# CX3_Camera_Layout.net
KiCad netlist of a schematic drawn in Altium Designer
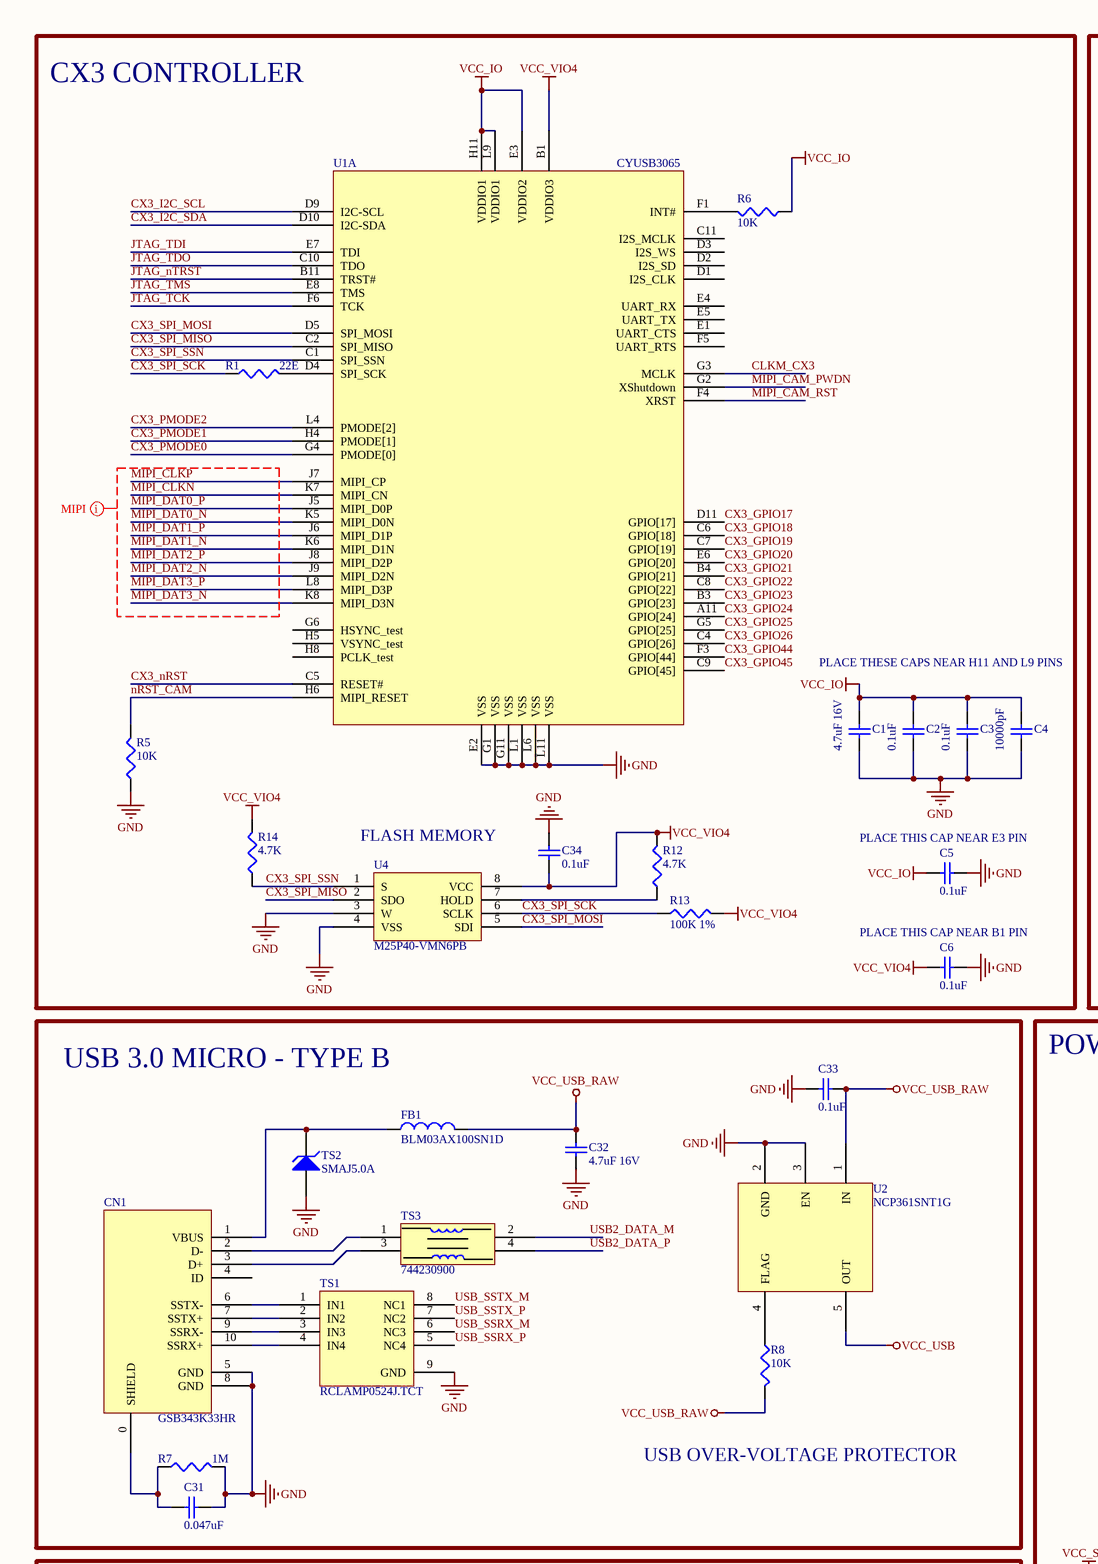
[diagram p0: CX3_Camera_Layout.SchDoc, top left]
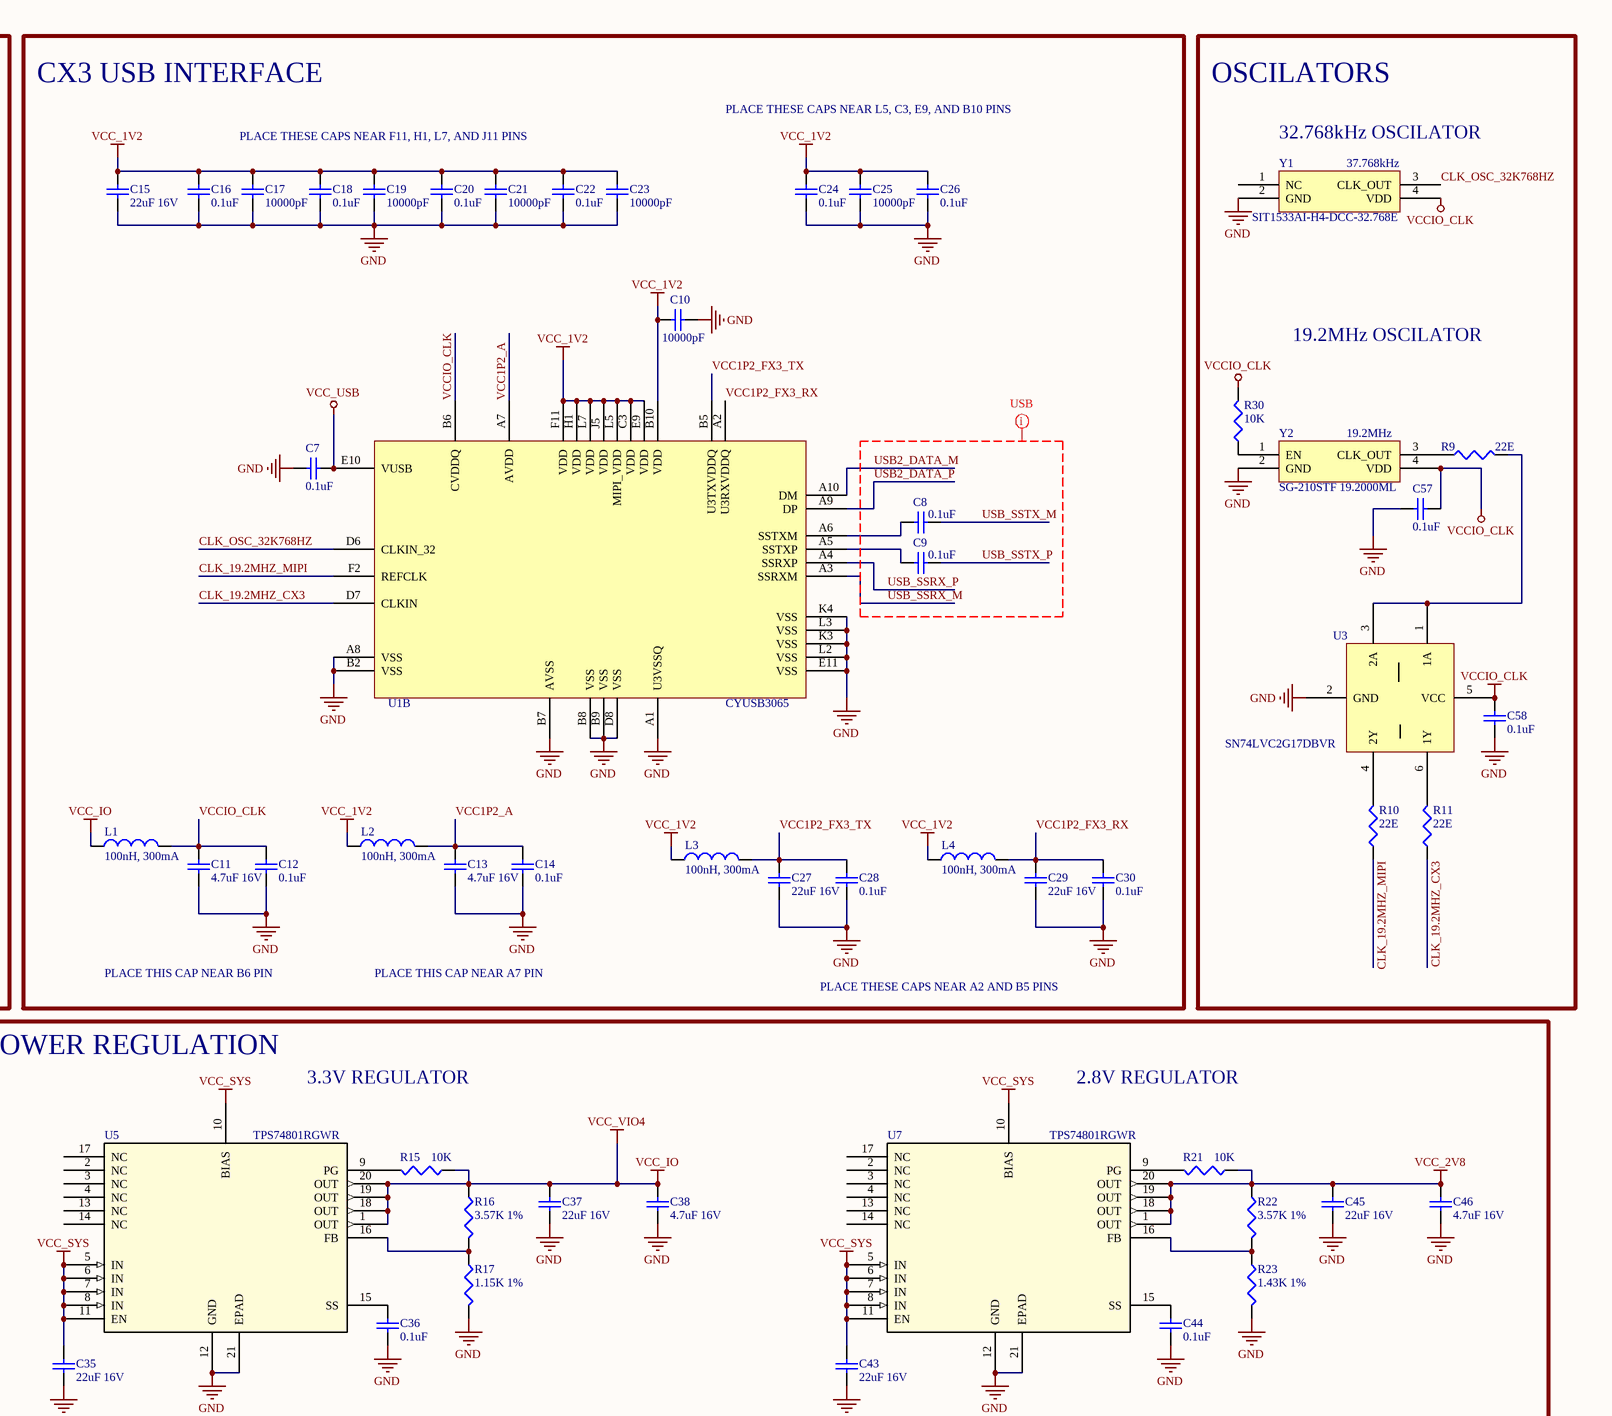
[diagram p1: CX3_Camera_Layout.SchDoc, top right]
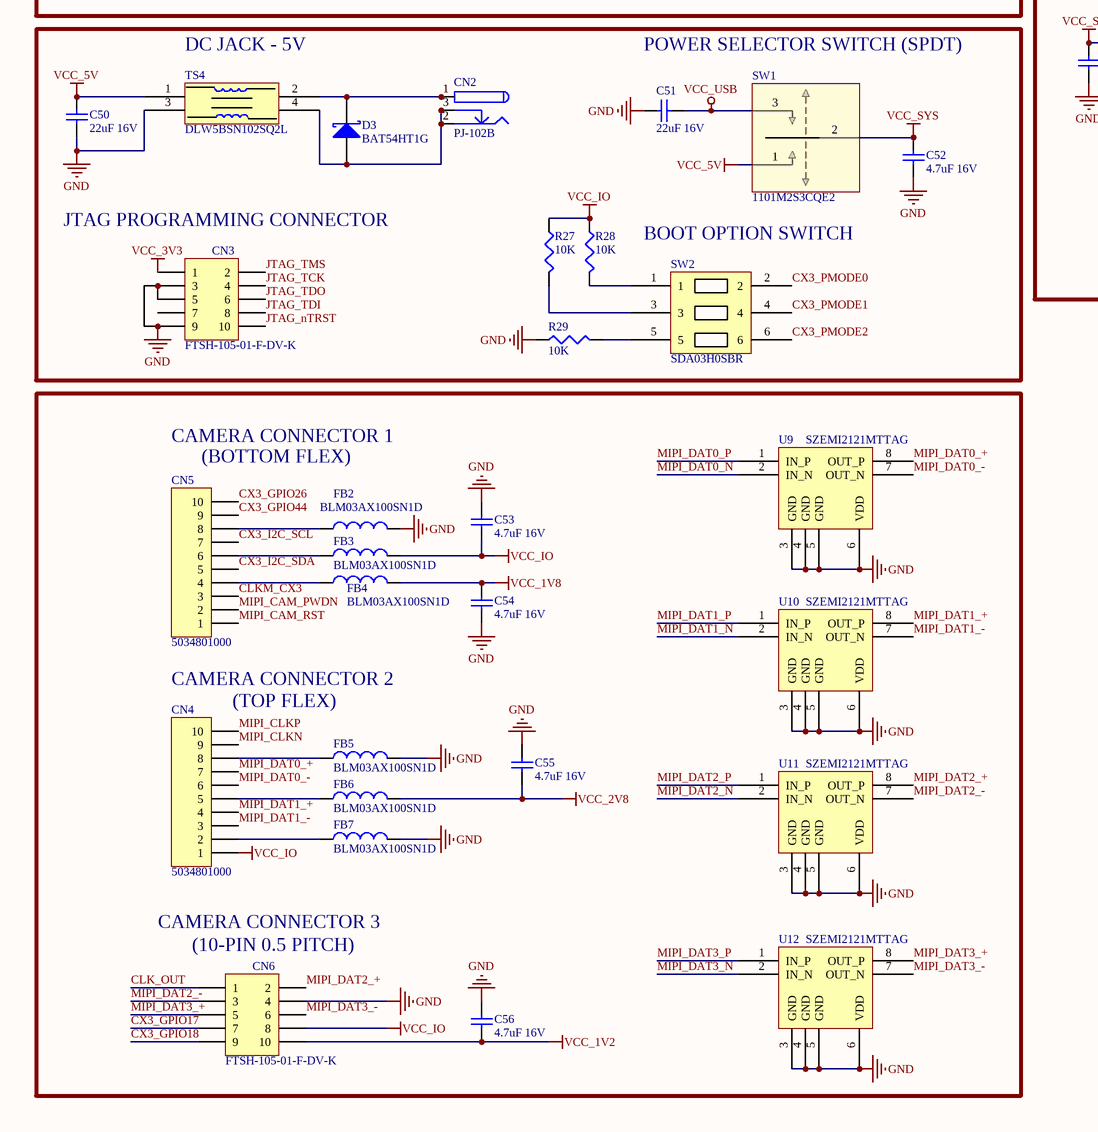
[diagram p2: CX3_Camera_Layout.SchDoc, bottom left]
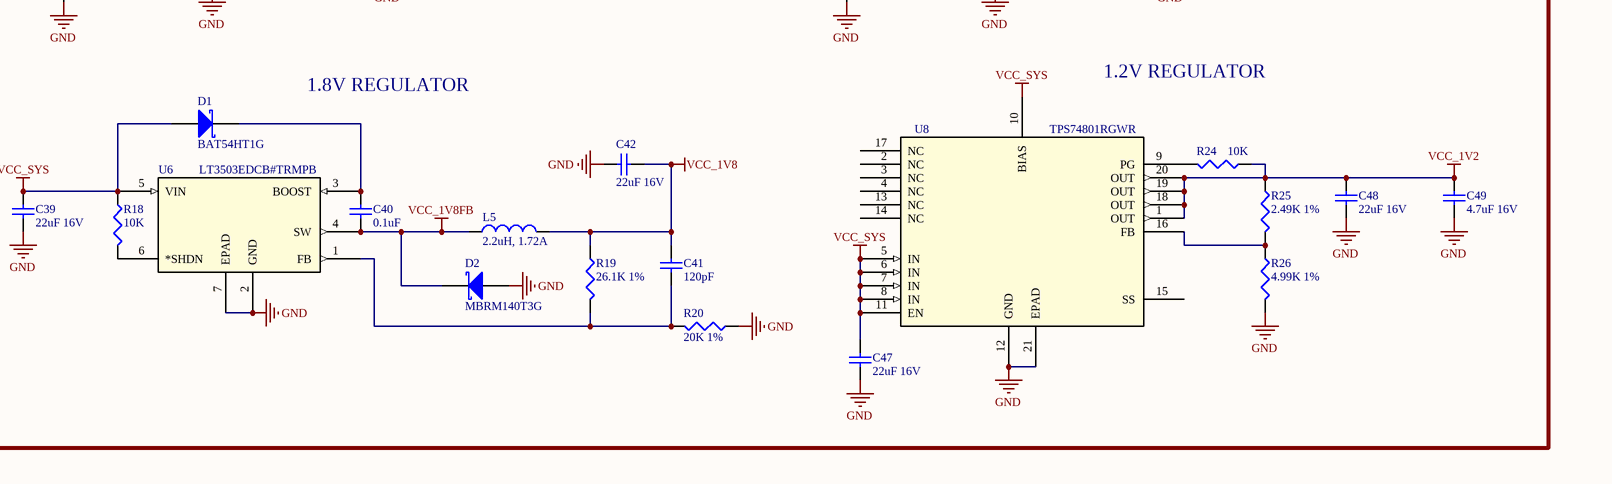
[diagram p3: CX3_Camera_Layout.SchDoc, bottom right]

(export (version "E")
  (design (tool "Eeschema 10.0.6"))
  (components
    (comp (ref "C1")
      (value "4.7uF 16V")
      (footprint "1608[0603]")
      (description "Capacitor (Semiconductor SIM Model)")
      (fields (field (name "PUBLISHER") "Altium Limited"))
      (libsource (lib "Miscellaneous Devices") (part "Cap Semi"))
    )
    (comp (ref "C2")
      (value "0.1uF")
      (footprint "0402")
      (description "Capacitor (Semiconductor SIM Model)")
      (fields (field (name "PUBLISHER") "Altium Limited"))
      (libsource (lib "Miscellaneous Devices") (part "Cap Semi"))
    )
    (comp (ref "C3")
      (value "0.1uF")
      (footprint "0402")
      (description "Capacitor (Semiconductor SIM Model)")
      (fields (field (name "PUBLISHER") "Altium Limited"))
      (libsource (lib "Miscellaneous Devices") (part "Cap Semi"))
    )
    (comp (ref "C4")
      (value "10000pF")
      (footprint "0402")
      (description "Capacitor (Semiconductor SIM Model)")
      (fields (field (name "PUBLISHER") "Altium Limited"))
      (libsource (lib "Miscellaneous Devices") (part "Cap Semi"))
    )
    (comp (ref "C5")
      (value "0.1uF")
      (footprint "0402")
      (description "Capacitor (Semiconductor SIM Model)")
      (fields (field (name "PUBLISHER") "Altium Limited"))
      (libsource (lib "Miscellaneous Devices") (part "Cap Semi"))
    )
    (comp (ref "C6")
      (value "0.1uF")
      (footprint "0402")
      (description "Capacitor (Semiconductor SIM Model)")
      (fields (field (name "PUBLISHER") "Altium Limited"))
      (libsource (lib "Miscellaneous Devices") (part "Cap Semi"))
    )
    (comp (ref "C7")
      (value "0.1uF")
      (footprint "0402")
      (description "Capacitor (Semiconductor SIM Model)")
      (fields (field (name "PUBLISHER") "Altium Limited"))
      (libsource (lib "Miscellaneous Devices") (part "Cap Semi"))
    )
    (comp (ref "C8")
      (value "0.1uF")
      (footprint "0402")
      (description "Capacitor (Semiconductor SIM Model)")
      (fields (field (name "PUBLISHER") "Altium Limited"))
      (libsource (lib "Miscellaneous Devices") (part "Cap Semi"))
    )
    (comp (ref "C9")
      (value "0.1uF")
      (footprint "0402")
      (description "Capacitor (Semiconductor SIM Model)")
      (fields (field (name "PUBLISHER") "Altium Limited"))
      (libsource (lib "Miscellaneous Devices") (part "Cap Semi"))
    )
    (comp (ref "C10")
      (value "10000pF")
      (footprint "0402")
      (description "Capacitor (Semiconductor SIM Model)")
      (fields (field (name "PUBLISHER") "Altium Limited"))
      (libsource (lib "Miscellaneous Devices") (part "Cap Semi"))
    )
    (comp (ref "C11")
      (value "4.7uF 16V")
      (footprint "1608[0603]")
      (description "Capacitor (Semiconductor SIM Model)")
      (fields (field (name "PUBLISHER") "Altium Limited"))
      (libsource (lib "Miscellaneous Devices") (part "Cap Semi"))
    )
    (comp (ref "C12")
      (value "0.1uF")
      (footprint "0402")
      (description "Capacitor (Semiconductor SIM Model)")
      (fields (field (name "PUBLISHER") "Altium Limited"))
      (libsource (lib "Miscellaneous Devices") (part "Cap Semi"))
    )
    (comp (ref "C13")
      (value "4.7uF 16V")
      (footprint "1608[0603]")
      (description "Capacitor (Semiconductor SIM Model)")
      (fields (field (name "PUBLISHER") "Altium Limited"))
      (libsource (lib "Miscellaneous Devices") (part "Cap Semi"))
    )
    (comp (ref "C14")
      (value "0.1uF")
      (footprint "0402")
      (description "Capacitor (Semiconductor SIM Model)")
      (fields (field (name "PUBLISHER") "Altium Limited"))
      (libsource (lib "Miscellaneous Devices") (part "Cap Semi"))
    )
    (comp (ref "C15")
      (value "22uF 16V")
      (footprint "1608[0603]")
      (description "Capacitor (Semiconductor SIM Model)")
      (fields (field (name "PUBLISHER") "Altium Limited"))
      (libsource (lib "Miscellaneous Devices") (part "Cap Semi"))
    )
    (comp (ref "C16")
      (value "0.1uF")
      (footprint "0402")
      (description "Capacitor (Semiconductor SIM Model)")
      (fields (field (name "PUBLISHER") "Altium Limited"))
      (libsource (lib "Miscellaneous Devices") (part "Cap Semi"))
    )
    (comp (ref "C17")
      (value "10000pF")
      (footprint "0402")
      (description "Capacitor (Semiconductor SIM Model)")
      (fields (field (name "PUBLISHER") "Altium Limited"))
      (libsource (lib "Miscellaneous Devices") (part "Cap Semi"))
    )
    (comp (ref "C18")
      (value "0.1uF")
      (footprint "0402")
      (description "Capacitor (Semiconductor SIM Model)")
      (fields (field (name "PUBLISHER") "Altium Limited"))
      (libsource (lib "Miscellaneous Devices") (part "Cap Semi"))
    )
    (comp (ref "C19")
      (value "10000pF")
      (footprint "0402")
      (description "Capacitor (Semiconductor SIM Model)")
      (fields (field (name "PUBLISHER") "Altium Limited"))
      (libsource (lib "Miscellaneous Devices") (part "Cap Semi"))
    )
    (comp (ref "C20")
      (value "0.1uF")
      (footprint "0402")
      (description "Capacitor (Semiconductor SIM Model)")
      (fields (field (name "PUBLISHER") "Altium Limited"))
      (libsource (lib "Miscellaneous Devices") (part "Cap Semi"))
    )
    (comp (ref "C21")
      (value "10000pF")
      (footprint "0402")
      (description "Capacitor (Semiconductor SIM Model)")
      (fields (field (name "PUBLISHER") "Altium Limited"))
      (libsource (lib "Miscellaneous Devices") (part "Cap Semi"))
    )
    (comp (ref "C22")
      (value "0.1uF")
      (footprint "0402")
      (description "Capacitor (Semiconductor SIM Model)")
      (fields (field (name "PUBLISHER") "Altium Limited"))
      (libsource (lib "Miscellaneous Devices") (part "Cap Semi"))
    )
    (comp (ref "C23")
      (value "10000pF")
      (footprint "0402")
      (description "Capacitor (Semiconductor SIM Model)")
      (fields (field (name "PUBLISHER") "Altium Limited"))
      (libsource (lib "Miscellaneous Devices") (part "Cap Semi"))
    )
    (comp (ref "C24")
      (value "0.1uF")
      (footprint "0402")
      (description "Capacitor (Semiconductor SIM Model)")
      (fields (field (name "PUBLISHER") "Altium Limited"))
      (libsource (lib "Miscellaneous Devices") (part "Cap Semi"))
    )
    (comp (ref "C25")
      (value "10000pF")
      (footprint "0402")
      (description "Capacitor (Semiconductor SIM Model)")
      (fields (field (name "PUBLISHER") "Altium Limited"))
      (libsource (lib "Miscellaneous Devices") (part "Cap Semi"))
    )
    (comp (ref "C26")
      (value "0.1uF")
      (footprint "0402")
      (description "Capacitor (Semiconductor SIM Model)")
      (fields (field (name "PUBLISHER") "Altium Limited"))
      (libsource (lib "Miscellaneous Devices") (part "Cap Semi"))
    )
    (comp (ref "C27")
      (value "22uF 16V")
      (footprint "1608[0603]")
      (description "Capacitor (Semiconductor SIM Model)")
      (fields (field (name "PUBLISHER") "Altium Limited"))
      (libsource (lib "Miscellaneous Devices") (part "Cap Semi"))
    )
    (comp (ref "C28")
      (value "0.1uF")
      (footprint "0402")
      (description "Capacitor (Semiconductor SIM Model)")
      (fields (field (name "PUBLISHER") "Altium Limited"))
      (libsource (lib "Miscellaneous Devices") (part "Cap Semi"))
    )
    (comp (ref "C29")
      (value "22uF 16V")
      (footprint "1608[0603]")
      (description "Capacitor (Semiconductor SIM Model)")
      (fields (field (name "PUBLISHER") "Altium Limited"))
      (libsource (lib "Miscellaneous Devices") (part "Cap Semi"))
    )
    (comp (ref "C30")
      (value "0.1uF")
      (footprint "0402")
      (description "Capacitor (Semiconductor SIM Model)")
      (fields (field (name "PUBLISHER") "Altium Limited"))
      (libsource (lib "Miscellaneous Devices") (part "Cap Semi"))
    )
    (comp (ref "C31")
      (value "0.047uF")
      (footprint "C1210")
      (description "Capacitor (Semiconductor SIM Model)")
      (fields (field (name "PUBLISHER") "Altium Limited"))
      (libsource (lib "Miscellaneous Devices") (part "Cap Semi"))
    )
    (comp (ref "C32")
      (value "4.7uF 16V")
      (footprint "1608[0603]")
      (description "Capacitor (Semiconductor SIM Model)")
      (fields (field (name "PUBLISHER") "Altium Limited"))
      (libsource (lib "Miscellaneous Devices") (part "Cap Semi"))
    )
    (comp (ref "C33")
      (value "0.1uF")
      (footprint "0402")
      (description "Capacitor (Semiconductor SIM Model)")
      (fields (field (name "PUBLISHER") "Altium Limited"))
      (libsource (lib "Miscellaneous Devices") (part "Cap Semi"))
    )
    (comp (ref "C34")
      (value "0.1uF")
      (footprint "0402")
      (description "Capacitor (Semiconductor SIM Model)")
      (fields (field (name "PUBLISHER") "Altium Limited"))
      (libsource (lib "Miscellaneous Devices") (part "Cap Semi"))
    )
    (comp (ref "C35")
      (value "22uF 16V")
      (footprint "1608[0603]")
      (description "Capacitor (Semiconductor SIM Model)")
      (fields (field (name "PUBLISHER") "Altium Limited"))
      (libsource (lib "Miscellaneous Devices") (part "Cap Semi"))
    )
    (comp (ref "C36")
      (value "0.1uF")
      (footprint "0402")
      (description "Capacitor (Semiconductor SIM Model)")
      (fields (field (name "PUBLISHER") "Altium Limited"))
      (libsource (lib "Miscellaneous Devices") (part "Cap Semi"))
    )
    (comp (ref "C37")
      (value "22uF 16V")
      (footprint "1608[0603]")
      (description "Capacitor (Semiconductor SIM Model)")
      (fields (field (name "PUBLISHER") "Altium Limited"))
      (libsource (lib "Miscellaneous Devices") (part "Cap Semi"))
    )
    (comp (ref "C38")
      (value "4.7uF 16V")
      (footprint "1608[0603]")
      (description "Capacitor (Semiconductor SIM Model)")
      (fields (field (name "PUBLISHER") "Altium Limited"))
      (libsource (lib "Miscellaneous Devices") (part "Cap Semi"))
    )
    (comp (ref "C39")
      (value "22uF 16V")
      (footprint "1608[0603]")
      (description "Capacitor (Semiconductor SIM Model)")
      (fields (field (name "PUBLISHER") "Altium Limited"))
      (libsource (lib "Miscellaneous Devices") (part "Cap Semi"))
    )
    (comp (ref "C40")
      (value "0.1uF")
      (footprint "0402")
      (description "Capacitor (Semiconductor SIM Model)")
      (fields (field (name "PUBLISHER") "Altium Limited"))
      (libsource (lib "Miscellaneous Devices") (part "Cap Semi"))
    )
    (comp (ref "C41")
      (value "120pF")
      (footprint "0402")
      (description "Capacitor (Semiconductor SIM Model)")
      (fields (field (name "PUBLISHER") "Altium Limited"))
      (libsource (lib "Miscellaneous Devices") (part "Cap Semi"))
    )
    (comp (ref "C42")
      (value "22uF 16V")
      (footprint "1608[0603]")
      (description "Capacitor (Semiconductor SIM Model)")
      (fields (field (name "PUBLISHER") "Altium Limited"))
      (libsource (lib "Miscellaneous Devices") (part "Cap Semi"))
    )
    (comp (ref "C43")
      (value "22uF 16V")
      (footprint "1608[0603]")
      (description "Capacitor (Semiconductor SIM Model)")
      (fields (field (name "PUBLISHER") "Altium Limited"))
      (libsource (lib "Miscellaneous Devices") (part "Cap Semi"))
    )
    (comp (ref "C44")
      (value "0.1uF")
      (footprint "0402")
      (description "Capacitor (Semiconductor SIM Model)")
      (fields (field (name "PUBLISHER") "Altium Limited"))
      (libsource (lib "Miscellaneous Devices") (part "Cap Semi"))
    )
    (comp (ref "C45")
      (value "22uF 16V")
      (footprint "1608[0603]")
      (description "Capacitor (Semiconductor SIM Model)")
      (fields (field (name "PUBLISHER") "Altium Limited"))
      (libsource (lib "Miscellaneous Devices") (part "Cap Semi"))
    )
    (comp (ref "C46")
      (value "4.7uF 16V")
      (footprint "1608[0603]")
      (description "Capacitor (Semiconductor SIM Model)")
      (fields (field (name "PUBLISHER") "Altium Limited"))
      (libsource (lib "Miscellaneous Devices") (part "Cap Semi"))
    )
    (comp (ref "C47")
      (value "22uF 16V")
      (footprint "1608[0603]")
      (description "Capacitor (Semiconductor SIM Model)")
      (fields (field (name "PUBLISHER") "Altium Limited"))
      (libsource (lib "Miscellaneous Devices") (part "Cap Semi"))
    )
    (comp (ref "C48")
      (value "22uF 16V")
      (footprint "1608[0603]")
      (description "Capacitor (Semiconductor SIM Model)")
      (fields (field (name "PUBLISHER") "Altium Limited"))
      (libsource (lib "Miscellaneous Devices") (part "Cap Semi"))
    )
    (comp (ref "C49")
      (value "4.7uF 16V")
      (footprint "1608[0603]")
      (description "Capacitor (Semiconductor SIM Model)")
      (fields (field (name "PUBLISHER") "Altium Limited"))
      (libsource (lib "Miscellaneous Devices") (part "Cap Semi"))
    )
    (comp (ref "C50")
      (value "22uF 16V")
      (footprint "1608[0603]")
      (description "Capacitor (Semiconductor SIM Model)")
      (fields (field (name "PUBLISHER") "Altium Limited"))
      (libsource (lib "Miscellaneous Devices") (part "Cap Semi"))
    )
    (comp (ref "C51")
      (value "22uF 16V")
      (footprint "C0805")
      (description "Capacitor (Semiconductor SIM Model)")
      (fields (field (name "PUBLISHER") "Altium Limited"))
      (libsource (lib "Miscellaneous Devices") (part "Cap Semi"))
    )
    (comp (ref "C52")
      (value "4.7uF 16V")
      (footprint "C0805")
      (description "Capacitor (Semiconductor SIM Model)")
      (fields (field (name "PUBLISHER") "Altium Limited"))
      (libsource (lib "Miscellaneous Devices") (part "Cap Semi"))
    )
    (comp (ref "C53")
      (value "4.7uF 16V")
      (footprint "1608[0603]")
      (description "Capacitor (Semiconductor SIM Model)")
      (fields (field (name "PUBLISHER") "Altium Limited"))
      (libsource (lib "Miscellaneous Devices") (part "Cap Semi"))
    )
    (comp (ref "C54")
      (value "4.7uF 16V")
      (footprint "1608[0603]")
      (description "Capacitor (Semiconductor SIM Model)")
      (fields (field (name "PUBLISHER") "Altium Limited"))
      (libsource (lib "Miscellaneous Devices") (part "Cap Semi"))
    )
    (comp (ref "C55")
      (value "4.7uF 16V")
      (footprint "1608[0603]")
      (description "Capacitor (Semiconductor SIM Model)")
      (fields (field (name "PUBLISHER") "Altium Limited"))
      (libsource (lib "Miscellaneous Devices") (part "Cap Semi"))
    )
    (comp (ref "C56")
      (value "4.7uF 16V")
      (footprint "1608[0603]")
      (description "Capacitor (Semiconductor SIM Model)")
      (fields (field (name "PUBLISHER") "Altium Limited"))
      (libsource (lib "Miscellaneous Devices") (part "Cap Semi"))
    )
    (comp (ref "C57")
      (value "0.1uF")
      (footprint "0402")
      (description "Capacitor (Semiconductor SIM Model)")
      (fields (field (name "PUBLISHER") "Altium Limited"))
      (libsource (lib "Miscellaneous Devices") (part "Cap Semi"))
    )
    (comp (ref "C58")
      (value "0.1uF")
      (footprint "0402")
      (description "Capacitor (Semiconductor SIM Model)")
      (fields (field (name "PUBLISHER") "Altium Limited"))
      (libsource (lib "Miscellaneous Devices") (part "Cap Semi"))
    )
    (comp (ref "CN1")
      (value "GSB343K33HR")
      (footprint "USB3MicroB")
      (libsource (lib "CX3_Camera") (part "GSB343K33HR"))
    )
    (comp (ref "CN2")
      (value "PJ-102B")
      (footprint "KLD-0202")
      (description "Low Voltage Power Supply Connector")
      (fields (field (name "PUBLISHER") "Altium Limited"))
      (libsource (lib "Miscellaneous Connectors") (part "PWR2.5"))
    )
    (comp (ref "CN3")
      (value "FTSH-105-01-F-DV-K")
      (footprint "FTSH-105-01-F-DV-K")
      (description "Header, 5-Pin, Dual row")
      (fields (field (name "PUBLISHER") "Altium Limited"))
      (libsource (lib "Miscellaneous Connectors") (part "MHDR2X5"))
    )
    (comp (ref "CN4")
      (value "5034801000")
      (footprint "5034801000")
      (description "Header, 10-Pin")
      (fields (field (name "PUBLISHER") "Altium Limited"))
      (libsource (lib "Miscellaneous Connectors") (part "Header 10"))
    )
    (comp (ref "CN5")
      (value "5034801000")
      (footprint "5034801000")
      (description "Header, 10-Pin")
      (fields (field (name "PUBLISHER") "Altium Limited"))
      (libsource (lib "Miscellaneous Connectors") (part "Header 10"))
    )
    (comp (ref "CN6")
      (value "FTSH-105-01-F-DV-K")
      (footprint "FTSH-105-01-F-DV-K")
      (description "Header, 5-Pin, Dual row")
      (fields (field (name "PUBLISHER") "Altium Limited"))
      (libsource (lib "Miscellaneous Connectors") (part "MHDR2X5"))
    )
    (comp (ref "D1")
      (value "BAT54HT1G")
      (footprint "SOD-323")
      (description "Silicon AF Schottky Rectifier Diode")
      (fields (field (name "PUBLISHER") "Altium Limited"))
      (libsource (lib "Infineon Discrete Diode") (part "BAT60B"))
    )
    (comp (ref "D2")
      (value "MBRM140T3G")
      (footprint "DO-216AA")
      (description "Silicon AF Schottky Rectifier Diode")
      (fields (field (name "PUBLISHER") "Altium Limited"))
      (libsource (lib "Infineon Discrete Diode") (part "BAT60B"))
    )
    (comp (ref "D3")
      (value "BAT54HT1G")
      (footprint "DO-214AC")
      (description "Silicon AF Schottky Rectifier Diode")
      (fields (field (name "PUBLISHER") "Altium Limited"))
      (libsource (lib "Infineon Discrete Diode") (part "BAT60B"))
    )
    (comp (ref "FB1")
      (value "BLM03AX100SN1D")
      (footprint "1608[0603]")
      (description "Inductor")
      (fields (field (name "PUBLISHER") "Altium Limited"))
      (libsource (lib "Miscellaneous Devices") (part "Inductor"))
    )
    (comp (ref "FB2")
      (value "BLM03AX100SN1D")
      (footprint "0603")
      (description "Inductor")
      (fields (field (name "PUBLISHER") "Altium Limited"))
      (libsource (lib "Miscellaneous Devices") (part "Inductor"))
    )
    (comp (ref "FB3")
      (value "BLM03AX100SN1D")
      (footprint "0603")
      (description "Inductor")
      (fields (field (name "PUBLISHER") "Altium Limited"))
      (libsource (lib "Miscellaneous Devices") (part "Inductor"))
    )
    (comp (ref "FB4")
      (value "BLM03AX100SN1D")
      (footprint "0603")
      (description "Inductor")
      (fields (field (name "PUBLISHER") "Altium Limited"))
      (libsource (lib "Miscellaneous Devices") (part "Inductor"))
    )
    (comp (ref "FB5")
      (value "BLM03AX100SN1D")
      (footprint "0603")
      (description "Inductor")
      (fields (field (name "PUBLISHER") "Altium Limited"))
      (libsource (lib "Miscellaneous Devices") (part "Inductor"))
    )
    (comp (ref "FB6")
      (value "BLM03AX100SN1D")
      (footprint "0603")
      (description "Inductor")
      (fields (field (name "PUBLISHER") "Altium Limited"))
      (libsource (lib "Miscellaneous Devices") (part "Inductor"))
    )
    (comp (ref "FB7")
      (value "BLM03AX100SN1D")
      (footprint "0603")
      (description "Inductor")
      (fields (field (name "PUBLISHER") "Altium Limited"))
      (libsource (lib "Miscellaneous Devices") (part "Inductor"))
    )
    (comp (ref "L1")
      (value "100nH, 300mA")
      (footprint "0603")
      (description "Inductor")
      (fields (field (name "PUBLISHER") "Altium Limited"))
      (libsource (lib "Miscellaneous Devices") (part "Inductor"))
    )
    (comp (ref "L2")
      (value "100nH, 300mA")
      (footprint "0603")
      (description "Inductor")
      (fields (field (name "PUBLISHER") "Altium Limited"))
      (libsource (lib "Miscellaneous Devices") (part "Inductor"))
    )
    (comp (ref "L3")
      (value "100nH, 300mA")
      (footprint "0603")
      (description "Inductor")
      (fields (field (name "PUBLISHER") "Altium Limited"))
      (libsource (lib "Miscellaneous Devices") (part "Inductor"))
    )
    (comp (ref "L4")
      (value "100nH, 300mA")
      (footprint "0603")
      (description "Inductor")
      (fields (field (name "PUBLISHER") "Altium Limited"))
      (libsource (lib "Miscellaneous Devices") (part "Inductor"))
    )
    (comp (ref "L5")
      (value "2.2uH, 1.72A")
      (footprint "0603")
      (description "Inductor")
      (fields (field (name "PUBLISHER") "Altium Limited"))
      (libsource (lib "Miscellaneous Devices") (part "Inductor"))
    )
    (comp (ref "R1")
      (value "22E")
      (footprint "0402")
      (description "Resistor")
      (fields (field (name "PUBLISHER") "Altium Limited"))
      (libsource (lib "Miscellaneous Devices") (part "Res3"))
    )
    (comp (ref "R5")
      (value "10K")
      (footprint "0402")
      (description "Resistor")
      (fields (field (name "PUBLISHER") "Altium Limited"))
      (libsource (lib "Miscellaneous Devices") (part "Res3"))
    )
    (comp (ref "R6")
      (value "10K")
      (footprint "0402")
      (description "Resistor")
      (fields (field (name "PUBLISHER") "Altium Limited"))
      (libsource (lib "Miscellaneous Devices") (part "Res3"))
    )
    (comp (ref "R7")
      (value "1M")
      (footprint "0402")
      (description "Resistor")
      (fields (field (name "PUBLISHER") "Altium Limited"))
      (libsource (lib "Miscellaneous Devices") (part "Res3"))
    )
    (comp (ref "R8")
      (value "10K")
      (footprint "0402")
      (description "Resistor")
      (fields (field (name "PUBLISHER") "Altium Limited"))
      (libsource (lib "Miscellaneous Devices") (part "Res3"))
    )
    (comp (ref "R9")
      (value "22E")
      (footprint "J1-0603")
      (description "Resistor")
      (fields (field (name "PUBLISHER") "Altium Limited"))
      (libsource (lib "Miscellaneous Devices") (part "Res3"))
    )
    (comp (ref "R10")
      (value "22E")
      (footprint "0402")
      (description "Resistor")
      (fields (field (name "PUBLISHER") "Altium Limited"))
      (libsource (lib "Miscellaneous Devices") (part "Res3"))
    )
    (comp (ref "R11")
      (value "22E")
      (footprint "0402")
      (description "Resistor")
      (fields (field (name "PUBLISHER") "Altium Limited"))
      (libsource (lib "Miscellaneous Devices") (part "Res3"))
    )
    (comp (ref "R12")
      (value "4.7K")
      (footprint "0402")
      (description "Resistor")
      (fields (field (name "PUBLISHER") "Altium Limited"))
      (libsource (lib "Miscellaneous Devices") (part "Res3"))
    )
    (comp (ref "R13")
      (value "100K 1%")
      (footprint "0402")
      (description "Resistor")
      (fields (field (name "PUBLISHER") "Altium Limited"))
      (libsource (lib "Miscellaneous Devices") (part "Res3"))
    )
    (comp (ref "R14")
      (value "4.7K")
      (footprint "0402")
      (description "Resistor")
      (fields (field (name "PUBLISHER") "Altium Limited"))
      (libsource (lib "Miscellaneous Devices") (part "Res3"))
    )
    (comp (ref "R15")
      (value "10K")
      (footprint "0402")
      (description "Resistor")
      (fields (field (name "PUBLISHER") "Altium Limited"))
      (libsource (lib "Miscellaneous Devices") (part "Res3"))
    )
    (comp (ref "R16")
      (value "3.57K 1%")
      (footprint "0402")
      (description "Resistor")
      (fields (field (name "PUBLISHER") "Altium Limited"))
      (libsource (lib "Miscellaneous Devices") (part "Res3"))
    )
    (comp (ref "R17")
      (value "1.15K 1%")
      (footprint "0402")
      (description "Resistor")
      (fields (field (name "PUBLISHER") "Altium Limited"))
      (libsource (lib "Miscellaneous Devices") (part "Res3"))
    )
    (comp (ref "R18")
      (value "10K")
      (footprint "0402")
      (description "Resistor")
      (fields (field (name "PUBLISHER") "Altium Limited"))
      (libsource (lib "Miscellaneous Devices") (part "Res3"))
    )
    (comp (ref "R19")
      (value "26.1K 1%")
      (footprint "0402")
      (description "Resistor")
      (fields (field (name "PUBLISHER") "Altium Limited"))
      (libsource (lib "Miscellaneous Devices") (part "Res3"))
    )
    (comp (ref "R20")
      (value "20K 1%")
      (footprint "0402")
      (description "Resistor")
      (fields (field (name "PUBLISHER") "Altium Limited"))
      (libsource (lib "Miscellaneous Devices") (part "Res3"))
    )
    (comp (ref "R21")
      (value "10K")
      (footprint "0402")
      (description "Resistor")
      (fields (field (name "PUBLISHER") "Altium Limited"))
      (libsource (lib "Miscellaneous Devices") (part "Res3"))
    )
    (comp (ref "R22")
      (value "3.57K 1%")
      (footprint "0402")
      (description "Resistor")
      (fields (field (name "PUBLISHER") "Altium Limited"))
      (libsource (lib "Miscellaneous Devices") (part "Res3"))
    )
    (comp (ref "R23")
      (value "1.43K 1%")
      (footprint "0402")
      (description "Resistor")
      (fields (field (name "PUBLISHER") "Altium Limited"))
      (libsource (lib "Miscellaneous Devices") (part "Res3"))
    )
    (comp (ref "R24")
      (value "10K")
      (footprint "0402")
      (description "Resistor")
      (fields (field (name "PUBLISHER") "Altium Limited"))
      (libsource (lib "Miscellaneous Devices") (part "Res3"))
    )
    (comp (ref "R25")
      (value "2.49K 1%")
      (footprint "0402")
      (description "Resistor")
      (fields (field (name "PUBLISHER") "Altium Limited"))
      (libsource (lib "Miscellaneous Devices") (part "Res3"))
    )
    (comp (ref "R26")
      (value "4.99K 1%")
      (footprint "0402")
      (description "Resistor")
      (fields (field (name "PUBLISHER") "Altium Limited"))
      (libsource (lib "Miscellaneous Devices") (part "Res3"))
    )
    (comp (ref "R27")
      (value "10K")
      (footprint "0402")
      (description "Resistor")
      (fields (field (name "PUBLISHER") "Altium Limited"))
      (libsource (lib "Miscellaneous Devices") (part "Res3"))
    )
    (comp (ref "R28")
      (value "10K")
      (footprint "0402")
      (description "Resistor")
      (fields (field (name "PUBLISHER") "Altium Limited"))
      (libsource (lib "Miscellaneous Devices") (part "Res3"))
    )
    (comp (ref "R29")
      (value "10K")
      (footprint "0402")
      (description "Resistor")
      (fields (field (name "PUBLISHER") "Altium Limited"))
      (libsource (lib "Miscellaneous Devices") (part "Res3"))
    )
    (comp (ref "R30")
      (value "10K")
      (footprint "0402")
      (description "Resistor")
      (fields (field (name "PUBLISHER") "Altium Limited"))
      (libsource (lib "Miscellaneous Devices") (part "Res3"))
    )
    (comp (ref "SW1")
      (value "1101M2S3CQE2")
      (footprint "1101M2S3CQE2")
      (description "Imported")
      (fields (field (name "COPYRIGHT") "Copyright (C) 2015 Accelerated Designs. All rights reserved"))
      (libsource (lib "CX3_Camera") (part "1101M2S3CQE2"))
    )
    (comp (ref "SW2")
      (value "SDA03H0SBR")
      (footprint "SDA03H0SBR")
      (libsource (lib "CX3_Camera") (part "SDA03H0SBR"))
    )
    (comp (ref "TS1")
      (value "RCLAMP0524J.TCT")
      (footprint "RCLAMP0524J")
      (libsource (lib "CX3_Camera") (part "RCLAMP0524J"))
    )
    (comp (ref "TS2")
      (value "SMAJ5.0A")
      (footprint "DO-214AC")
      (description "Silicon Zener Diode")
      (fields (field (name "PUBLISHER") "Altium Limited"))
      (libsource (lib "Vishay Lite-On Discrete Diode") (part "DL5243B"))
    )
    (comp (ref "TS3") (value "744230900") (libsource (lib "CX3_Camera") (part "CHOKE_COM")))
    (comp (ref "TS4")
      (value "DLW5BSN102SQ2L")
      (footprint "SRF0504-102Y")
      (libsource (lib "CX3_Camera") (part "CHOKE_COM"))
    )
    (comp (ref "U1")
      (value "CYUSB3065")
      (footprint "BGA121C80P11X11_1000X1000X170B30N")
      (description "Cypress CX3")
      (libsource (lib "CX3_Camera") (part "CYUSB3065"))
    )
    (comp (ref "U2")
      (value "NCP361SNT1G")
      (footprint "SOT-23-5")
      (libsource (lib "CX3_Camera") (part "NCP361SNT1G"))
    )
    (comp (ref "U3")
      (value "SN74LVC2G17DBVR")
      (footprint "SOT-23_A_N")
      (libsource (lib "CX3_Camera") (part "SN74LVC2G17DBVR"))
    )
    (comp (ref "U4")
      (value "M25P40-VMN6PB")
      (footprint "SO8_M")
      (libsource (lib "CX3_Camera") (part "M25P40"))
    )
    (comp (ref "U5")
      (value "TPS74801RGWR")
      (footprint "RGW20_3P15X3P15")
      (description "Imported")
      (fields
        (field (name "GENERIC_PART_NUMBER") "TPS74801")
        (field (name "MANUFACTURER") "Texas Instruments")
        (field (name "COPYRIGHT") "Copyright (C) 2015 Accelerated Designs. All rights reserved")
      )
      (libsource (lib "CX3_Camera") (part "TPS74801RGWR"))
    )
    (comp (ref "U6")
      (value "LT3503EDCB#TRMPB")
      (footprint "DFN-6_DCB")
      (description "Imported")
      (fields
        (field (name "MANUFACTURER_PART_NUMBER") "lt3503edcb#trmpbf")
        (field (name "COPYRIGHT") "Copyright (C) 2016 Accelerated Designs. All rights reserved")
      )
      (libsource (lib "CX3_Camera") (part "LT3503EDCB#TRMPB"))
    )
    (comp (ref "U7")
      (value "TPS74801RGWR")
      (footprint "RGW20_3P15X3P15")
      (description "Imported")
      (fields
        (field (name "GENERIC_PART_NUMBER") "TPS74801")
        (field (name "MANUFACTURER") "Texas Instruments")
        (field (name "COPYRIGHT") "Copyright (C) 2015 Accelerated Designs. All rights reserved")
      )
      (libsource (lib "CX3_Camera") (part "TPS74801RGWR"))
    )
    (comp (ref "U8")
      (value "TPS74801RGWR")
      (footprint "RGW20_3P15X3P15")
      (description "Imported")
      (fields
        (field (name "GENERIC_PART_NUMBER") "TPS74801")
        (field (name "MANUFACTURER") "Texas Instruments")
        (field (name "COPYRIGHT") "Copyright (C) 2015 Accelerated Designs. All rights reserved")
      )
      (libsource (lib "CX3_Camera") (part "TPS74801RGWR"))
    )
    (comp (ref "U9")
      (value "SZEMI2121MTTAG")
      (footprint "SZEMI2121MTTAG")
      (libsource (lib "CX3_Camera") (part "SZEMI2121MTTAG"))
    )
    (comp (ref "U10")
      (value "SZEMI2121MTTAG")
      (footprint "SZEMI2121MTTAG")
      (libsource (lib "CX3_Camera") (part "SZEMI2121MTTAG"))
    )
    (comp (ref "U11")
      (value "SZEMI2121MTTAG")
      (footprint "SZEMI2121MTTAG")
      (libsource (lib "CX3_Camera") (part "SZEMI2121MTTAG"))
    )
    (comp (ref "U12")
      (value "SZEMI2121MTTAG")
      (footprint "SZEMI2121MTTAG")
      (libsource (lib "CX3_Camera") (part "SZEMI2121MTTAG"))
    )
    (comp (ref "Y1")
      (value "SIT1533AI-H4-DCC-32.768E")
      (footprint "SiT1533")
      (fields (field (name "ALTIUM_VALUE") "37.768kHz"))
      (libsource (lib "CX3_Camera") (part "OSCILATOR_32kHz"))
    )
    (comp (ref "Y2")
      (value "SG-210STF 19.2000ML")
      (footprint "SG5032")
      (fields (field (name "ALTIUM_VALUE") "19.2MHz"))
      (libsource (lib "CX3_Camera") (part "OSCILLATOR"))
    )
  )
  (nets
    (net (code "1") (name "/CLKM_CX3") (class "Default")
      (node (ref "CN5") (pin "3") (pinfunction "3_3") (pintype "passive"))
      (node (ref "U1") (pin "G3") (pinfunction "MCLK_G3") (pintype "passive"))
    )
    (net (code "2") (name "/CLK_19.2MHZ_CX3") (class "Default")
      (node (ref "R11") (pin "1") (pinfunction "1_1") (pintype "passive"))
      (node (ref "U1") (pin "D7") (pinfunction "CLKIN_D7") (pintype "passive"))
    )
    (net (code "3") (name "/CLK_19.2MHZ_MIPI") (class "Default")
      (node (ref "R10") (pin "1") (pinfunction "1_1") (pintype "passive"))
      (node (ref "U1") (pin "F2") (pinfunction "REFCLK_F2") (pintype "passive"))
    )
    (net (code "4") (name "/CLK_OSC_32K768HZ") (class "Default")
      (node (ref "U1") (pin "D6") (pinfunction "CLKIN_32_D6") (pintype "passive"))
      (node (ref "Y1") (pin "3") (pinfunction "CLK_OUT_3") (pintype "passive"))
    )
    (net (code "5") (name "/CLK_OUT") (class "Default")
      (node (ref "CN6") (pin "1") (pinfunction "1_1") (pintype "passive"))
    )
    (net (code "6") (name "/CX3_GPIO17") (class "Default")
      (node (ref "CN6") (pin "7") (pinfunction "7_7") (pintype "passive"))
      (node (ref "U1") (pin "D11") (pinfunction "GPIO[17]_D11") (pintype "passive"))
    )
    (net (code "7") (name "/CX3_GPIO18") (class "Default")
      (node (ref "CN6") (pin "9") (pinfunction "9_9") (pintype "passive"))
      (node (ref "U1") (pin "C6") (pinfunction "GPIO[18]_C6") (pintype "passive"))
    )
    (net (code "8") (name "/CX3_GPIO19") (class "Default")
      (node (ref "U1") (pin "C7") (pinfunction "GPIO[19]_C7") (pintype "passive"))
    )
    (net (code "9") (name "/CX3_GPIO20") (class "Default")
      (node (ref "U1") (pin "E6") (pinfunction "GPIO[20]_E6") (pintype "passive"))
    )
    (net (code "10") (name "/CX3_GPIO21") (class "Default")
      (node (ref "U1") (pin "B4") (pinfunction "GPIO[21]_B4") (pintype "passive"))
    )
    (net (code "11") (name "/CX3_GPIO22") (class "Default")
      (node (ref "U1") (pin "C8") (pinfunction "GPIO[22]_C8") (pintype "passive"))
    )
    (net (code "12") (name "/CX3_GPIO23") (class "Default")
      (node (ref "U1") (pin "B3") (pinfunction "GPIO[23]_B3") (pintype "passive"))
    )
    (net (code "13") (name "/CX3_GPIO24") (class "Default")
      (node (ref "U1") (pin "A11") (pinfunction "GPIO[24]_A11") (pintype "passive"))
    )
    (net (code "14") (name "/CX3_GPIO25") (class "Default")
      (node (ref "U1") (pin "G5") (pinfunction "GPIO[25]_G5") (pintype "passive"))
    )
    (net (code "15") (name "/CX3_GPIO26") (class "Default")
      (node (ref "CN5") (pin "10") (pinfunction "10_10") (pintype "passive"))
      (node (ref "U1") (pin "C4") (pinfunction "GPIO[26]_C4") (pintype "passive"))
    )
    (net (code "16") (name "/CX3_GPIO44") (class "Default")
      (node (ref "CN5") (pin "9") (pinfunction "9_9") (pintype "passive"))
      (node (ref "U1") (pin "F3") (pinfunction "GPIO[44]_F3") (pintype "passive"))
    )
    (net (code "17") (name "/CX3_GPIO45") (class "Default")
      (node (ref "U1") (pin "C9") (pinfunction "GPIO[45]_C9") (pintype "passive"))
    )
    (net (code "18") (name "/CX3_I2C_SCL") (class "Default")
      (node (ref "CN5") (pin "7") (pinfunction "7_7") (pintype "passive"))
      (node (ref "U1") (pin "D9") (pinfunction "I2C-SCL_D9") (pintype "passive"))
    )
    (net (code "19") (name "/CX3_I2C_SDA") (class "Default")
      (node (ref "CN5") (pin "5") (pinfunction "5_5") (pintype "passive"))
      (node (ref "U1") (pin "D10") (pinfunction "I2C-SDA_D10") (pintype "passive"))
    )
    (net (code "20") (name "/CX3_PMODE0") (class "Default")
      (node (ref "SW2") (pin "2") (pinfunction "2_2") (pintype "passive"))
      (node (ref "U1") (pin "G4") (pinfunction "PMODE[0]_G4") (pintype "passive"))
    )
    (net (code "21") (name "/CX3_PMODE1") (class "Default")
      (node (ref "SW2") (pin "4") (pinfunction "4_4") (pintype "passive"))
      (node (ref "U1") (pin "H4") (pinfunction "PMODE[1]_H4") (pintype "passive"))
    )
    (net (code "22") (name "/CX3_PMODE2") (class "Default")
      (node (ref "SW2") (pin "6") (pinfunction "6_6") (pintype "passive"))
      (node (ref "U1") (pin "L4") (pinfunction "PMODE[2]_L4") (pintype "passive"))
    )
    (net (code "23") (name "/CX3_SPI_MISO") (class "Default")
      (node (ref "U1") (pin "C2") (pinfunction "SPI_MISO_C2") (pintype "passive"))
      (node (ref "U4") (pin "2") (pinfunction "SDO_2") (pintype "passive"))
    )
    (net (code "24") (name "/CX3_SPI_MOSI") (class "Default")
      (node (ref "U1") (pin "D5") (pinfunction "SPI_MOSI_D5") (pintype "passive"))
      (node (ref "U4") (pin "5") (pinfunction "SDI_5") (pintype "passive"))
    )
    (net (code "25") (name "/CX3_SPI_SCK") (class "Default")
      (node (ref "R1") (pin "1") (pinfunction "1_1") (pintype "passive"))
      (node (ref "R13") (pin "1") (pinfunction "1_1") (pintype "passive"))
      (node (ref "U4") (pin "6") (pinfunction "SCLK_6") (pintype "passive"))
    )
    (net (code "26") (name "/CX3_SPI_SSN") (class "Default")
      (node (ref "R14") (pin "1") (pinfunction "1_1") (pintype "passive"))
      (node (ref "U1") (pin "C1") (pinfunction "SPI_SSN_C1") (pintype "passive"))
      (node (ref "U4") (pin "1") (pinfunction "S_1") (pintype "passive"))
    )
    (net (code "27") (name "/CX3_nRST") (class "Default")
      (node (ref "U1") (pin "C5") (pinfunction "RESET#_C5") (pintype "passive"))
    )
    (net (code "28") (name "/JTAG_TCK") (class "Default")
      (node (ref "CN3") (pin "4") (pinfunction "4_4") (pintype "passive"))
      (node (ref "U1") (pin "F6") (pinfunction "TCK_F6") (pintype "passive"))
    )
    (net (code "29") (name "/JTAG_TDI") (class "Default")
      (node (ref "CN3") (pin "8") (pinfunction "8_8") (pintype "passive"))
      (node (ref "U1") (pin "E7") (pinfunction "TDI_E7") (pintype "passive"))
    )
    (net (code "30") (name "/JTAG_TDO") (class "Default")
      (node (ref "CN3") (pin "6") (pinfunction "6_6") (pintype "passive"))
      (node (ref "U1") (pin "C10") (pinfunction "TDO_C10") (pintype "passive"))
    )
    (net (code "31") (name "/JTAG_TMS") (class "Default")
      (node (ref "CN3") (pin "2") (pinfunction "2_2") (pintype "passive"))
      (node (ref "U1") (pin "E8") (pinfunction "TMS_E8") (pintype "passive"))
    )
    (net (code "32") (name "/JTAG_nTRST") (class "Default")
      (node (ref "CN3") (pin "10") (pinfunction "10_10") (pintype "passive"))
      (node (ref "U1") (pin "B11") (pinfunction "TRST#_B11") (pintype "passive"))
    )
    (net (code "33") (name "/MIPI_CAM_PWDN") (class "Default")
      (node (ref "CN5") (pin "2") (pinfunction "2_2") (pintype "passive"))
      (node (ref "U1") (pin "G2") (pinfunction "XShutdown_G2") (pintype "passive"))
    )
    (net (code "34") (name "/MIPI_CAM_RST") (class "Default")
      (node (ref "CN5") (pin "1") (pinfunction "1_1") (pintype "passive"))
      (node (ref "U1") (pin "F4") (pinfunction "XRST_F4") (pintype "passive"))
    )
    (net (code "35") (name "/MIPI_CLKN") (class "Default")
      (node (ref "CN4") (pin "9") (pinfunction "9_9") (pintype "passive"))
      (node (ref "U1") (pin "K7") (pinfunction "MIPI_CN_K7") (pintype "passive"))
    )
    (net (code "36") (name "/MIPI_CLKP") (class "Default")
      (node (ref "CN4") (pin "10") (pinfunction "10_10") (pintype "passive"))
      (node (ref "U1") (pin "J7") (pinfunction "MIPI_CP_J7") (pintype "passive"))
    )
    (net (code "37") (name "/MIPI_DAT0_+") (class "Default")
      (node (ref "CN4") (pin "7") (pinfunction "7_7") (pintype "passive"))
      (node (ref "U9") (pin "8") (pinfunction "OUT_P_8") (pintype "passive"))
    )
    (net (code "38") (name "/MIPI_DAT0_-") (class "Default")
      (node (ref "CN4") (pin "6") (pinfunction "6_6") (pintype "passive"))
      (node (ref "U9") (pin "7") (pinfunction "OUT_N_7") (pintype "passive"))
    )
    (net (code "39") (name "/MIPI_DAT0_N") (class "Default")
      (node (ref "U1") (pin "K5") (pinfunction "MIPI_D0N_K5") (pintype "passive"))
      (node (ref "U9") (pin "2") (pinfunction "IN_N_2") (pintype "passive"))
    )
    (net (code "40") (name "/MIPI_DAT0_P") (class "Default")
      (node (ref "U1") (pin "J5") (pinfunction "MIPI_D0P_J5") (pintype "passive"))
      (node (ref "U9") (pin "1") (pinfunction "IN_P_1") (pintype "passive"))
    )
    (net (code "41") (name "/MIPI_DAT1_+") (class "Default")
      (node (ref "CN4") (pin "4") (pinfunction "4_4") (pintype "passive"))
      (node (ref "U10") (pin "8") (pinfunction "OUT_P_8") (pintype "passive"))
    )
    (net (code "42") (name "/MIPI_DAT1_-") (class "Default")
      (node (ref "CN4") (pin "3") (pinfunction "3_3") (pintype "passive"))
      (node (ref "U10") (pin "7") (pinfunction "OUT_N_7") (pintype "passive"))
    )
    (net (code "43") (name "/MIPI_DAT1_N") (class "Default")
      (node (ref "U1") (pin "K6") (pinfunction "MIPI_D1N_K6") (pintype "passive"))
      (node (ref "U10") (pin "2") (pinfunction "IN_N_2") (pintype "passive"))
    )
    (net (code "44") (name "/MIPI_DAT1_P") (class "Default")
      (node (ref "U1") (pin "J6") (pinfunction "MIPI_D1P_J6") (pintype "passive"))
      (node (ref "U10") (pin "1") (pinfunction "IN_P_1") (pintype "passive"))
    )
    (net (code "45") (name "/MIPI_DAT2_+") (class "Default")
      (node (ref "CN6") (pin "2") (pinfunction "2_2") (pintype "passive"))
      (node (ref "U11") (pin "8") (pinfunction "OUT_P_8") (pintype "passive"))
    )
    (net (code "46") (name "/MIPI_DAT2_-") (class "Default")
      (node (ref "CN6") (pin "3") (pinfunction "3_3") (pintype "passive"))
      (node (ref "U11") (pin "7") (pinfunction "OUT_N_7") (pintype "passive"))
    )
    (net (code "47") (name "/MIPI_DAT2_N") (class "Default")
      (node (ref "U1") (pin "J9") (pinfunction "MIPI_D2N_J9") (pintype "passive"))
      (node (ref "U11") (pin "2") (pinfunction "IN_N_2") (pintype "passive"))
    )
    (net (code "48") (name "/MIPI_DAT2_P") (class "Default")
      (node (ref "U1") (pin "J8") (pinfunction "MIPI_D2P_J8") (pintype "passive"))
      (node (ref "U11") (pin "1") (pinfunction "IN_P_1") (pintype "passive"))
    )
    (net (code "49") (name "/MIPI_DAT3_+") (class "Default")
      (node (ref "CN6") (pin "5") (pinfunction "5_5") (pintype "passive"))
      (node (ref "U12") (pin "8") (pinfunction "OUT_P_8") (pintype "passive"))
    )
    (net (code "50") (name "/MIPI_DAT3_-") (class "Default")
      (node (ref "CN6") (pin "6") (pinfunction "6_6") (pintype "passive"))
      (node (ref "U12") (pin "7") (pinfunction "OUT_N_7") (pintype "passive"))
    )
    (net (code "51") (name "/MIPI_DAT3_N") (class "Default")
      (node (ref "U1") (pin "K8") (pinfunction "MIPI_D3N_K8") (pintype "passive"))
      (node (ref "U12") (pin "2") (pinfunction "IN_N_2") (pintype "passive"))
    )
    (net (code "52") (name "/MIPI_DAT3_P") (class "Default")
      (node (ref "U1") (pin "L8") (pinfunction "MIPI_D3P_L8") (pintype "passive"))
      (node (ref "U12") (pin "1") (pinfunction "IN_P_1") (pintype "passive"))
    )
    (net (code "53") (name "/USB2_DATA_M") (class "Default")
      (node (ref "TS3") (pin "2") (pintype "passive"))
      (node (ref "U1") (pin "A10") (pinfunction "DM_A10") (pintype "passive"))
    )
    (net (code "54") (name "/USB2_DATA_P") (class "Default")
      (node (ref "TS3") (pin "4") (pintype "passive"))
      (node (ref "U1") (pin "A9") (pinfunction "DP_A9") (pintype "passive"))
    )
    (net (code "55") (name "/USB_SSRX_M") (class "Default")
      (node (ref "TS1") (pin "6") (pinfunction "NC3_6") (pintype "passive"))
      (node (ref "U1") (pin "A3") (pinfunction "SSRXM_A3") (pintype "passive"))
    )
    (net (code "56") (name "/USB_SSRX_P") (class "Default")
      (node (ref "TS1") (pin "5") (pinfunction "NC4_5") (pintype "passive"))
      (node (ref "U1") (pin "A4") (pinfunction "SSRXP_A4") (pintype "passive"))
    )
    (net (code "57") (name "/USB_SSTX_M") (class "Default")
      (node (ref "C8") (pin "2") (pinfunction "2_2") (pintype "passive"))
      (node (ref "TS1") (pin "8") (pinfunction "NC1_8") (pintype "passive"))
    )
    (net (code "58") (name "/USB_SSTX_P") (class "Default")
      (node (ref "C9") (pin "2") (pinfunction "2_2") (pintype "passive"))
      (node (ref "TS1") (pin "7") (pinfunction "NC2_7") (pintype "passive"))
    )
    (net (code "59") (name "/VCC1P2_A") (class "Default")
      (node (ref "C13") (pin "2") (pinfunction "2_2") (pintype "passive"))
      (node (ref "C14") (pin "1") (pinfunction "1_1") (pintype "passive"))
      (node (ref "L2") (pin "2") (pinfunction "2_2") (pintype "passive"))
      (node (ref "U1") (pin "A7") (pinfunction "AVDD_A7") (pintype "passive"))
    )
    (net (code "60") (name "/VCC1P2_FX3_RX") (class "Default")
      (node (ref "C29") (pin "2") (pinfunction "2_2") (pintype "passive"))
      (node (ref "C30") (pin "1") (pinfunction "1_1") (pintype "passive"))
      (node (ref "L4") (pin "2") (pinfunction "2_2") (pintype "passive"))
      (node (ref "U1") (pin "A2") (pinfunction "U3RXVDDQ_A2") (pintype "passive"))
    )
    (net (code "61") (name "/VCC1P2_FX3_TX") (class "Default")
      (node (ref "C27") (pin "2") (pinfunction "2_2") (pintype "passive"))
      (node (ref "C28") (pin "1") (pinfunction "1_1") (pintype "passive"))
      (node (ref "L3") (pin "2") (pinfunction "2_2") (pintype "passive"))
      (node (ref "U1") (pin "B5") (pinfunction "U3TXVDDQ_B5") (pintype "passive"))
    )
    (net (code "62") (name "/nRST_CAM") (class "Default")
      (node (ref "R5") (pin "2") (pinfunction "2_2") (pintype "passive"))
      (node (ref "U1") (pin "H6") (pinfunction "MIPI_RESET_H6") (pintype "passive"))
    )
    (net (code "63") (name "GND") (class "Default")
      (node (ref "C1") (pin "2") (pinfunction "2_2") (pintype "passive"))
      (node (ref "C10") (pin "2") (pinfunction "2_2") (pintype "passive"))
      (node (ref "C11") (pin "1") (pinfunction "1_1") (pintype "passive"))
      (node (ref "C12") (pin "2") (pinfunction "2_2") (pintype "passive"))
      (node (ref "C13") (pin "1") (pinfunction "1_1") (pintype "passive"))
      (node (ref "C14") (pin "2") (pinfunction "2_2") (pintype "passive"))
      (node (ref "C15") (pin "1") (pinfunction "1_1") (pintype "passive"))
      (node (ref "C16") (pin "1") (pinfunction "1_1") (pintype "passive"))
      (node (ref "C17") (pin "1") (pinfunction "1_1") (pintype "passive"))
      (node (ref "C18") (pin "1") (pinfunction "1_1") (pintype "passive"))
      (node (ref "C19") (pin "1") (pinfunction "1_1") (pintype "passive"))
      (node (ref "C2") (pin "2") (pinfunction "2_2") (pintype "passive"))
      (node (ref "C20") (pin "1") (pinfunction "1_1") (pintype "passive"))
      (node (ref "C21") (pin "1") (pinfunction "1_1") (pintype "passive"))
      (node (ref "C22") (pin "1") (pinfunction "1_1") (pintype "passive"))
      (node (ref "C23") (pin "1") (pinfunction "1_1") (pintype "passive"))
      (node (ref "C24") (pin "1") (pinfunction "1_1") (pintype "passive"))
      (node (ref "C25") (pin "1") (pinfunction "1_1") (pintype "passive"))
      (node (ref "C26") (pin "1") (pinfunction "1_1") (pintype "passive"))
      (node (ref "C27") (pin "1") (pinfunction "1_1") (pintype "passive"))
      (node (ref "C28") (pin "2") (pinfunction "2_2") (pintype "passive"))
      (node (ref "C29") (pin "1") (pinfunction "1_1") (pintype "passive"))
      (node (ref "C3") (pin "2") (pinfunction "2_2") (pintype "passive"))
      (node (ref "C30") (pin "2") (pinfunction "2_2") (pintype "passive"))
      (node (ref "C31") (pin "2") (pinfunction "2_2") (pintype "passive"))
      (node (ref "C32") (pin "1") (pinfunction "1_1") (pintype "passive"))
      (node (ref "C33") (pin "1") (pinfunction "1_1") (pintype "passive"))
      (node (ref "C34") (pin "2") (pinfunction "2_2") (pintype "passive"))
      (node (ref "C35") (pin "1") (pinfunction "1_1") (pintype "passive"))
      (node (ref "C36") (pin "1") (pinfunction "1_1") (pintype "passive"))
      (node (ref "C37") (pin "1") (pinfunction "1_1") (pintype "passive"))
      (node (ref "C38") (pin "1") (pinfunction "1_1") (pintype "passive"))
      (node (ref "C39") (pin "2") (pinfunction "2_2") (pintype "passive"))
      (node (ref "C4") (pin "2") (pinfunction "2_2") (pintype "passive"))
      (node (ref "C42") (pin "1") (pinfunction "1_1") (pintype "passive"))
      (node (ref "C43") (pin "1") (pinfunction "1_1") (pintype "passive"))
      (node (ref "C44") (pin "1") (pinfunction "1_1") (pintype "passive"))
      (node (ref "C45") (pin "1") (pinfunction "1_1") (pintype "passive"))
      (node (ref "C46") (pin "1") (pinfunction "1_1") (pintype "passive"))
      (node (ref "C47") (pin "1") (pinfunction "1_1") (pintype "passive"))
      (node (ref "C48") (pin "1") (pinfunction "1_1") (pintype "passive"))
      (node (ref "C49") (pin "1") (pinfunction "1_1") (pintype "passive"))
      (node (ref "C5") (pin "2") (pinfunction "2_2") (pintype "passive"))
      (node (ref "C50") (pin "1") (pinfunction "1_1") (pintype "passive"))
      (node (ref "C51") (pin "1") (pinfunction "1_1") (pintype "passive"))
      (node (ref "C52") (pin "1") (pinfunction "1_1") (pintype "passive"))
      (node (ref "C53") (pin "2") (pinfunction "2_2") (pintype "passive"))
      (node (ref "C54") (pin "1") (pinfunction "1_1") (pintype "passive"))
      (node (ref "C55") (pin "2") (pinfunction "2_2") (pintype "passive"))
      (node (ref "C56") (pin "2") (pinfunction "2_2") (pintype "passive"))
      (node (ref "C57") (pin "1") (pinfunction "1_1") (pintype "passive"))
      (node (ref "C58") (pin "2") (pinfunction "2_2") (pintype "passive"))
      (node (ref "C6") (pin "2") (pinfunction "2_2") (pintype "passive"))
      (node (ref "C7") (pin "1") (pinfunction "1_1") (pintype "passive"))
      (node (ref "CN1") (pin "5") (pinfunction "GND_5") (pintype "passive"))
      (node (ref "CN1") (pin "8") (pinfunction "GND_8") (pintype "passive"))
      (node (ref "CN3") (pin "3") (pinfunction "3_3") (pintype "passive"))
      (node (ref "CN3") (pin "5") (pinfunction "5_5") (pintype "passive"))
      (node (ref "CN3") (pin "9") (pinfunction "9_9") (pintype "passive"))
      (node (ref "CN6") (pin "4") (pinfunction "4_4") (pintype "passive"))
      (node (ref "D2") (pin "2") (pinfunction "A_2") (pintype "passive"))
      (node (ref "FB2") (pin "2") (pinfunction "2_2") (pintype "passive"))
      (node (ref "FB5") (pin "2") (pinfunction "2_2") (pintype "passive"))
      (node (ref "FB7") (pin "2") (pinfunction "2_2") (pintype "passive"))
      (node (ref "R17") (pin "2") (pinfunction "2_2") (pintype "passive"))
      (node (ref "R20") (pin "1") (pinfunction "1_1") (pintype "passive"))
      (node (ref "R23") (pin "2") (pinfunction "2_2") (pintype "passive"))
      (node (ref "R26") (pin "2") (pinfunction "2_2") (pintype "passive"))
      (node (ref "R29") (pin "1") (pinfunction "1_1") (pintype "passive"))
      (node (ref "R5") (pin "1") (pinfunction "1_1") (pintype "passive"))
      (node (ref "R7") (pin "2") (pinfunction "2_2") (pintype "passive"))
      (node (ref "TS1") (pin "9") (pinfunction "GND_9") (pintype "passive"))
      (node (ref "TS2") (pin "1") (pinfunction "A_1") (pintype "passive"))
      (node (ref "TS4") (pin "3") (pintype "passive"))
      (node (ref "U1") (pin "A1") (pinfunction "U3VSSQ_A1") (pintype "passive"))
      (node (ref "U1") (pin "A8") (pinfunction "VSS_A8") (pintype "passive"))
      (node (ref "U1") (pin "B2") (pinfunction "VSS_B2") (pintype "passive"))
      (node (ref "U1") (pin "B7") (pinfunction "AVSS_B7") (pintype "passive"))
      (node (ref "U1") (pin "B8") (pinfunction "VSS_B8") (pintype "passive"))
      (node (ref "U1") (pin "B9") (pinfunction "VSS_B9") (pintype "passive"))
      (node (ref "U1") (pin "D8") (pinfunction "VSS_D8") (pintype "passive"))
      (node (ref "U1") (pin "E11") (pinfunction "VSS_E11") (pintype "passive"))
      (node (ref "U1") (pin "E2") (pinfunction "VSS_E2") (pintype "passive"))
      (node (ref "U1") (pin "G1") (pinfunction "VSS_G1") (pintype "passive"))
      (node (ref "U1") (pin "G11") (pinfunction "VSS_G11") (pintype "passive"))
      (node (ref "U1") (pin "K3") (pinfunction "VSS_K3") (pintype "passive"))
      (node (ref "U1") (pin "K4") (pinfunction "VSS_K4") (pintype "passive"))
      (node (ref "U1") (pin "L1") (pinfunction "VSS_L1") (pintype "passive"))
      (node (ref "U1") (pin "L11") (pinfunction "VSS_L11") (pintype "passive"))
      (node (ref "U1") (pin "L2") (pinfunction "VSS_L2") (pintype "passive"))
      (node (ref "U1") (pin "L3") (pinfunction "VSS_L3") (pintype "passive"))
      (node (ref "U1") (pin "L6") (pinfunction "VSS_L6") (pintype "passive"))
      (node (ref "U10") (pin "3") (pinfunction "GND_3") (pintype "passive"))
      (node (ref "U10") (pin "4") (pinfunction "GND_4") (pintype "passive"))
      (node (ref "U10") (pin "5") (pinfunction "GND_5") (pintype "passive"))
      (node (ref "U10") (pin "6") (pinfunction "VDD_6") (pintype "passive"))
      (node (ref "U11") (pin "3") (pinfunction "GND_3") (pintype "passive"))
      (node (ref "U11") (pin "4") (pinfunction "GND_4") (pintype "passive"))
      (node (ref "U11") (pin "5") (pinfunction "GND_5") (pintype "passive"))
      (node (ref "U11") (pin "6") (pinfunction "VDD_6") (pintype "passive"))
      (node (ref "U12") (pin "3") (pinfunction "GND_3") (pintype "passive"))
      (node (ref "U12") (pin "4") (pinfunction "GND_4") (pintype "passive"))
      (node (ref "U12") (pin "5") (pinfunction "GND_5") (pintype "passive"))
      (node (ref "U12") (pin "6") (pinfunction "VDD_6") (pintype "passive"))
      (node (ref "U2") (pin "2") (pinfunction "GND_2") (pintype "passive"))
      (node (ref "U2") (pin "3") (pinfunction "EN_3") (pintype "passive"))
      (node (ref "U3") (pin "2") (pinfunction "GND_2") (pintype "passive"))
      (node (ref "U4") (pin "3") (pinfunction "W_3") (pintype "passive"))
      (node (ref "U4") (pin "4") (pinfunction "VSS_4") (pintype "passive"))
      (node (ref "U5") (pin "12") (pinfunction "GND_12") (pintype "power_in"))
      (node (ref "U5") (pin "21") (pinfunction "EPAD_21") (pintype "passive"))
      (node (ref "U6") (pin "2") (pinfunction "GND_2") (pintype "power_in"))
      (node (ref "U6") (pin "7") (pinfunction "EPAD_7") (pintype "passive"))
      (node (ref "U7") (pin "12") (pinfunction "GND_12") (pintype "power_in"))
      (node (ref "U7") (pin "21") (pinfunction "EPAD_21") (pintype "passive"))
      (node (ref "U8") (pin "12") (pinfunction "GND_12") (pintype "power_in"))
      (node (ref "U8") (pin "21") (pinfunction "EPAD_21") (pintype "passive"))
      (node (ref "U9") (pin "3") (pinfunction "GND_3") (pintype "passive"))
      (node (ref "U9") (pin "4") (pinfunction "GND_4") (pintype "passive"))
      (node (ref "U9") (pin "5") (pinfunction "GND_5") (pintype "passive"))
      (node (ref "U9") (pin "6") (pinfunction "VDD_6") (pintype "passive"))
      (node (ref "Y1") (pin "2") (pinfunction "GND_2") (pintype "passive"))
      (node (ref "Y2") (pin "2") (pinfunction "GND_2") (pintype "passive"))
    )
    (net (code "64") (name "Net-(CN1-D+)") (class "Default")
      (node (ref "CN1") (pin "3") (pinfunction "D+_3") (pintype "passive"))
      (node (ref "TS3") (pin "3") (pintype "passive"))
    )
    (net (code "65") (name "Net-(CN1-D-)") (class "Default")
      (node (ref "CN1") (pin "2") (pinfunction "D-_2") (pintype "passive"))
      (node (ref "TS3") (pin "1") (pintype "passive"))
    )
    (net (code "66") (name "Net-(CN1-SHIELD)") (class "Default")
      (node (ref "C31") (pin "1") (pinfunction "1_1") (pintype "passive"))
      (node (ref "CN1") (pin "0") (pinfunction "SHIELD_0") (pintype "passive"))
      (node (ref "R7") (pin "1") (pinfunction "1_1") (pintype "passive"))
    )
    (net (code "67") (name "Net-(CN1-SSRX+)") (class "Default")
      (node (ref "CN1") (pin "10") (pinfunction "SSRX+_10") (pintype "passive"))
      (node (ref "TS1") (pin "4") (pinfunction "IN4_4") (pintype "passive"))
    )
    (net (code "68") (name "Net-(CN1-SSRX-)") (class "Default")
      (node (ref "CN1") (pin "9") (pinfunction "SSRX-_9") (pintype "passive"))
      (node (ref "TS1") (pin "3") (pinfunction "IN3_3") (pintype "passive"))
    )
    (net (code "69") (name "Net-(CN1-SSTX+)") (class "Default")
      (node (ref "CN1") (pin "7") (pinfunction "SSTX+_7") (pintype "passive"))
      (node (ref "TS1") (pin "2") (pinfunction "IN2_2") (pintype "passive"))
    )
    (net (code "70") (name "Net-(CN1-SSTX-)") (class "Default")
      (node (ref "CN1") (pin "6") (pinfunction "SSTX-_6") (pintype "passive"))
      (node (ref "TS1") (pin "1") (pinfunction "IN1_1") (pintype "passive"))
    )
    (net (code "71") (name "Net-(CN1-VBUS)") (class "Default")
      (node (ref "CN1") (pin "1") (pinfunction "VBUS_1") (pintype "passive"))
      (node (ref "FB1") (pin "1") (pinfunction "1_1") (pintype "passive"))
      (node (ref "TS2") (pin "2") (pinfunction "K_2") (pintype "passive"))
    )
    (net (code "72") (name "Net-(CN4-Pad2)") (class "Default")
      (node (ref "CN4") (pin "2") (pinfunction "2_2") (pintype "passive"))
      (node (ref "FB7") (pin "1") (pinfunction "1_1") (pintype "passive"))
    )
    (net (code "73") (name "Net-(CN4-Pad5)") (class "Default")
      (node (ref "CN4") (pin "5") (pinfunction "5_5") (pintype "passive"))
      (node (ref "FB6") (pin "1") (pinfunction "1_1") (pintype "passive"))
    )
    (net (code "74") (name "Net-(CN4-Pad8)") (class "Default")
      (node (ref "CN4") (pin "8") (pinfunction "8_8") (pintype "passive"))
      (node (ref "FB5") (pin "1") (pinfunction "1_1") (pintype "passive"))
    )
    (net (code "75") (name "Net-(CN5-Pad4)") (class "Default")
      (node (ref "CN5") (pin "4") (pinfunction "4_4") (pintype "passive"))
      (node (ref "FB4") (pin "1") (pinfunction "1_1") (pintype "passive"))
    )
    (net (code "76") (name "Net-(CN5-Pad6)") (class "Default")
      (node (ref "CN5") (pin "6") (pinfunction "6_6") (pintype "passive"))
      (node (ref "FB3") (pin "1") (pinfunction "1_1") (pintype "passive"))
    )
    (net (code "77") (name "Net-(CN5-Pad8)") (class "Default")
      (node (ref "CN5") (pin "8") (pinfunction "8_8") (pintype "passive"))
      (node (ref "FB2") (pin "1") (pinfunction "1_1") (pintype "passive"))
    )
    (net (code "78") (name "Net-(D1-K)") (class "Default")
      (node (ref "C40") (pin "1") (pinfunction "1_1") (pintype "passive"))
      (node (ref "D1") (pin "1") (pinfunction "K_1") (pintype "passive"))
      (node (ref "U6") (pin "3") (pinfunction "BOOST_3") (pintype "input"))
    )
    (net (code "79") (name "Net-(D3-A)") (class "Default")
      (node (ref "CN2") (pin "2") (pinfunction "2_2") (pintype "power_in"))
      (node (ref "CN2") (pin "2A") (pinfunction "2A_2A") (pintype "power_in"))
      (node (ref "CN2") (pin "2B") (pinfunction "2B_2B") (pintype "power_in"))
      (node (ref "CN2") (pin "3") (pinfunction "3_3") (pintype "power_in"))
      (node (ref "CN2") (pin "3A") (pinfunction "3A_3A") (pintype "power_in"))
      (node (ref "CN2") (pin "3B") (pinfunction "3B_3B") (pintype "power_in"))
      (node (ref "D3") (pin "2") (pinfunction "A_2") (pintype "passive"))
      (node (ref "TS4") (pin "4") (pintype "passive"))
    )
    (net (code "80") (name "Net-(D3-K)") (class "Default")
      (node (ref "CN2") (pin "1") (pinfunction "1_1") (pintype "power_in"))
      (node (ref "CN2") (pin "1A") (pinfunction "1A_1A") (pintype "power_in"))
      (node (ref "CN2") (pin "1B") (pinfunction "1B_1B") (pintype "power_in"))
      (node (ref "D3") (pin "1") (pinfunction "K_1") (pintype "passive"))
      (node (ref "TS4") (pin "2") (pintype "passive"))
    )
    (net (code "81") (name "Net-(R27-Pad2)") (class "Default")
      (node (ref "R27") (pin "2") (pinfunction "2_2") (pintype "passive"))
      (node (ref "SW2") (pin "3") (pinfunction "3_3") (pintype "passive"))
    )
    (net (code "82") (name "Net-(R28-Pad2)") (class "Default")
      (node (ref "R28") (pin "2") (pinfunction "2_2") (pintype "passive"))
      (node (ref "SW2") (pin "1") (pinfunction "1_1") (pintype "passive"))
    )
    (net (code "83") (name "Net-(R29-Pad2)") (class "Default")
      (node (ref "R29") (pin "2") (pinfunction "2_2") (pintype "passive"))
      (node (ref "SW2") (pin "5") (pinfunction "5_5") (pintype "passive"))
    )
    (net (code "84") (name "Net-(U1A-INT#)") (class "Default")
      (node (ref "R6") (pin "2") (pinfunction "2_2") (pintype "passive"))
      (node (ref "U1") (pin "F1") (pinfunction "INT#_F1") (pintype "passive"))
    )
    (net (code "85") (name "Net-(U1A-SPI_SCK)") (class "Default")
      (node (ref "R1") (pin "2") (pinfunction "2_2") (pintype "passive"))
      (node (ref "U1") (pin "D4") (pinfunction "SPI_SCK_D4") (pintype "passive"))
    )
    (net (code "86") (name "Net-(U1B-SSTXM)") (class "Default")
      (node (ref "C8") (pin "1") (pinfunction "1_1") (pintype "passive"))
      (node (ref "U1") (pin "A6") (pinfunction "SSTXM_A6") (pintype "passive"))
    )
    (net (code "87") (name "Net-(U1B-SSTXP)") (class "Default")
      (node (ref "C9") (pin "1") (pinfunction "1_1") (pintype "passive"))
      (node (ref "U1") (pin "A5") (pinfunction "SSTXP_A5") (pintype "passive"))
    )
    (net (code "88") (name "Net-(U2-FLAG)") (class "Default")
      (node (ref "R8") (pin "1") (pinfunction "1_1") (pintype "passive"))
      (node (ref "U2") (pin "4") (pinfunction "FLAG_4") (pintype "passive"))
    )
    (net (code "89") (name "Net-(U3-1A)") (class "Default")
      (node (ref "R9") (pin "2") (pinfunction "2_2") (pintype "passive"))
      (node (ref "U3") (pin "1") (pinfunction "1A_1") (pintype "passive"))
      (node (ref "U3") (pin "3") (pinfunction "2A_3") (pintype "passive"))
    )
    (net (code "90") (name "Net-(U3-1Y)") (class "Default")
      (node (ref "R11") (pin "2") (pinfunction "2_2") (pintype "passive"))
      (node (ref "U3") (pin "6") (pinfunction "1Y_6") (pintype "passive"))
    )
    (net (code "91") (name "Net-(U3-2Y)") (class "Default")
      (node (ref "R10") (pin "2") (pinfunction "2_2") (pintype "passive"))
      (node (ref "U3") (pin "4") (pinfunction "2Y_4") (pintype "passive"))
    )
    (net (code "92") (name "Net-(U4-HOLD)") (class "Default")
      (node (ref "R12") (pin "1") (pinfunction "1_1") (pintype "passive"))
      (node (ref "U4") (pin "7") (pinfunction "HOLD_7") (pintype "passive"))
    )
    (net (code "93") (name "Net-(U5-FB)") (class "Default")
      (node (ref "R16") (pin "2") (pinfunction "2_2") (pintype "passive"))
      (node (ref "R17") (pin "1") (pinfunction "1_1") (pintype "passive"))
      (node (ref "U5") (pin "16") (pinfunction "FB_16") (pintype "passive"))
    )
    (net (code "94") (name "Net-(U5-PG)") (class "Default")
      (node (ref "R15") (pin "2") (pinfunction "2_2") (pintype "passive"))
      (node (ref "U5") (pin "9") (pinfunction "PG_9") (pintype "passive"))
    )
    (net (code "95") (name "Net-(U5-SS)") (class "Default")
      (node (ref "C36") (pin "2") (pinfunction "2_2") (pintype "passive"))
      (node (ref "U5") (pin "15") (pinfunction "SS_15") (pintype "passive"))
    )
    (net (code "96") (name "Net-(U6-*SHDN)") (class "Default")
      (node (ref "R18") (pin "2") (pinfunction "2_2") (pintype "passive"))
      (node (ref "U6") (pin "6") (pinfunction "*SHDN_6") (pintype "passive"))
    )
    (net (code "97") (name "Net-(U6-FB)") (class "Default")
      (node (ref "C41") (pin "2") (pinfunction "2_2") (pintype "passive"))
      (node (ref "R19") (pin "2") (pinfunction "2_2") (pintype "passive"))
      (node (ref "R20") (pin "2") (pinfunction "2_2") (pintype "passive"))
      (node (ref "U6") (pin "1") (pinfunction "FB_1") (pintype "output"))
    )
    (net (code "98") (name "Net-(U7-FB)") (class "Default")
      (node (ref "R22") (pin "2") (pinfunction "2_2") (pintype "passive"))
      (node (ref "R23") (pin "1") (pinfunction "1_1") (pintype "passive"))
      (node (ref "U7") (pin "16") (pinfunction "FB_16") (pintype "passive"))
    )
    (net (code "99") (name "Net-(U7-PG)") (class "Default")
      (node (ref "R21") (pin "2") (pinfunction "2_2") (pintype "passive"))
      (node (ref "U7") (pin "9") (pinfunction "PG_9") (pintype "passive"))
    )
    (net (code "100") (name "Net-(U7-SS)") (class "Default")
      (node (ref "C44") (pin "2") (pinfunction "2_2") (pintype "passive"))
      (node (ref "U7") (pin "15") (pinfunction "SS_15") (pintype "passive"))
    )
    (net (code "101") (name "Net-(U8-FB)") (class "Default")
      (node (ref "R25") (pin "2") (pinfunction "2_2") (pintype "passive"))
      (node (ref "R26") (pin "1") (pinfunction "1_1") (pintype "passive"))
      (node (ref "U8") (pin "16") (pinfunction "FB_16") (pintype "passive"))
    )
    (net (code "102") (name "Net-(U8-PG)") (class "Default")
      (node (ref "R24") (pin "2") (pinfunction "2_2") (pintype "passive"))
      (node (ref "U8") (pin "9") (pinfunction "PG_9") (pintype "passive"))
    )
    (net (code "103") (name "Net-(Y2-CLK_OUT)") (class "Default")
      (node (ref "R9") (pin "1") (pinfunction "1_1") (pintype "passive"))
      (node (ref "Y2") (pin "3") (pinfunction "CLK_OUT_3") (pintype "passive"))
    )
    (net (code "104") (name "Net-(Y2-EN)") (class "Default")
      (node (ref "R30") (pin "1") (pinfunction "1_1") (pintype "passive"))
      (node (ref "Y2") (pin "1") (pinfunction "EN_1") (pintype "passive"))
    )
    (net (code "105") (name "VCCIO_CLK") (class "Default")
      (node (ref "C11") (pin "2") (pinfunction "2_2") (pintype "passive"))
      (node (ref "C12") (pin "1") (pinfunction "1_1") (pintype "passive"))
      (node (ref "C57") (pin "2") (pinfunction "2_2") (pintype "passive"))
      (node (ref "C58") (pin "1") (pinfunction "1_1") (pintype "passive"))
      (node (ref "L1") (pin "2") (pinfunction "2_2") (pintype "passive"))
      (node (ref "R30") (pin "2") (pinfunction "2_2") (pintype "passive"))
      (node (ref "U1") (pin "B6") (pinfunction "CVDDQ_B6") (pintype "passive"))
      (node (ref "U3") (pin "5") (pinfunction "VCC_5") (pintype "passive"))
      (node (ref "Y1") (pin "4") (pinfunction "VDD_4") (pintype "passive"))
      (node (ref "Y2") (pin "4") (pinfunction "VDD_4") (pintype "passive"))
    )
    (net (code "106") (name "VCC_1V2") (class "Default")
      (node (ref "C10") (pin "1") (pinfunction "1_1") (pintype "passive"))
      (node (ref "C15") (pin "2") (pinfunction "2_2") (pintype "passive"))
      (node (ref "C16") (pin "2") (pinfunction "2_2") (pintype "passive"))
      (node (ref "C17") (pin "2") (pinfunction "2_2") (pintype "passive"))
      (node (ref "C18") (pin "2") (pinfunction "2_2") (pintype "passive"))
      (node (ref "C19") (pin "2") (pinfunction "2_2") (pintype "passive"))
      (node (ref "C20") (pin "2") (pinfunction "2_2") (pintype "passive"))
      (node (ref "C21") (pin "2") (pinfunction "2_2") (pintype "passive"))
      (node (ref "C22") (pin "2") (pinfunction "2_2") (pintype "passive"))
      (node (ref "C23") (pin "2") (pinfunction "2_2") (pintype "passive"))
      (node (ref "C24") (pin "2") (pinfunction "2_2") (pintype "passive"))
      (node (ref "C25") (pin "2") (pinfunction "2_2") (pintype "passive"))
      (node (ref "C26") (pin "2") (pinfunction "2_2") (pintype "passive"))
      (node (ref "C48") (pin "2") (pinfunction "2_2") (pintype "passive"))
      (node (ref "C49") (pin "2") (pinfunction "2_2") (pintype "passive"))
      (node (ref "C56") (pin "1") (pinfunction "1_1") (pintype "passive"))
      (node (ref "CN6") (pin "10") (pinfunction "10_10") (pintype "passive"))
      (node (ref "L2") (pin "1") (pinfunction "1_1") (pintype "passive"))
      (node (ref "L3") (pin "1") (pinfunction "1_1") (pintype "passive"))
      (node (ref "L4") (pin "1") (pinfunction "1_1") (pintype "passive"))
      (node (ref "R24") (pin "1") (pinfunction "1_1") (pintype "passive"))
      (node (ref "R25") (pin "1") (pinfunction "1_1") (pintype "passive"))
      (node (ref "U1") (pin "B10") (pinfunction "VDD_B10") (pintype "passive"))
      (node (ref "U1") (pin "C3") (pinfunction "VDD_C3") (pintype "passive"))
      (node (ref "U1") (pin "E9") (pinfunction "VDD_E9") (pintype "passive"))
      (node (ref "U1") (pin "F11") (pinfunction "VDD_F11") (pintype "passive"))
      (node (ref "U1") (pin "H1") (pinfunction "VDD_H1") (pintype "passive"))
      (node (ref "U1") (pin "J5") (pinfunction "VDD_J5") (pintype "passive"))
      (node (ref "U1") (pin "L5") (pinfunction "MIPI_VDD_L5") (pintype "passive"))
      (node (ref "U1") (pin "L7") (pinfunction "VDD_L7") (pintype "passive"))
      (node (ref "U8") (pin "1") (pinfunction "OUT_1") (pintype "output"))
      (node (ref "U8") (pin "18") (pinfunction "OUT_18") (pintype "output"))
      (node (ref "U8") (pin "19") (pinfunction "OUT_19") (pintype "output"))
      (node (ref "U8") (pin "20") (pinfunction "OUT_20") (pintype "output"))
    )
    (net (code "107") (name "VCC_1V8") (class "Default")
      (node (ref "C41") (pin "1") (pinfunction "1_1") (pintype "passive"))
      (node (ref "C42") (pin "2") (pinfunction "2_2") (pintype "passive"))
      (node (ref "C54") (pin "2") (pinfunction "2_2") (pintype "passive"))
      (node (ref "FB4") (pin "2") (pinfunction "2_2") (pintype "passive"))
      (node (ref "L5") (pin "2") (pinfunction "2_2") (pintype "passive"))
      (node (ref "R19") (pin "1") (pinfunction "1_1") (pintype "passive"))
    )
    (net (code "108") (name "VCC_1V8FB") (class "Default")
      (node (ref "C40") (pin "2") (pinfunction "2_2") (pintype "passive"))
      (node (ref "D2") (pin "1") (pinfunction "K_1") (pintype "passive"))
      (node (ref "L5") (pin "1") (pinfunction "1_1") (pintype "passive"))
      (node (ref "U6") (pin "4") (pinfunction "SW_4") (pintype "output"))
    )
    (net (code "109") (name "VCC_2V8") (class "Default")
      (node (ref "C45") (pin "2") (pinfunction "2_2") (pintype "passive"))
      (node (ref "C46") (pin "2") (pinfunction "2_2") (pintype "passive"))
      (node (ref "C55") (pin "1") (pinfunction "1_1") (pintype "passive"))
      (node (ref "FB6") (pin "2") (pinfunction "2_2") (pintype "passive"))
      (node (ref "R21") (pin "1") (pinfunction "1_1") (pintype "passive"))
      (node (ref "R22") (pin "1") (pinfunction "1_1") (pintype "passive"))
      (node (ref "U7") (pin "1") (pinfunction "OUT_1") (pintype "output"))
      (node (ref "U7") (pin "18") (pinfunction "OUT_18") (pintype "output"))
      (node (ref "U7") (pin "19") (pinfunction "OUT_19") (pintype "output"))
      (node (ref "U7") (pin "20") (pinfunction "OUT_20") (pintype "output"))
    )
    (net (code "110") (name "VCC_3V3") (class "Default")
      (node (ref "CN3") (pin "1") (pinfunction "1_1") (pintype "passive"))
    )
    (net (code "111") (name "VCC_5V") (class "Default")
      (node (ref "C50") (pin "2") (pinfunction "2_2") (pintype "passive"))
      (node (ref "SW1") (pin "1") (pinfunction "1_1") (pintype "passive"))
      (node (ref "TS4") (pin "1") (pintype "passive"))
    )
    (net (code "112") (name "VCC_IO") (class "Default")
      (node (ref "C1") (pin "1") (pinfunction "1_1") (pintype "passive"))
      (node (ref "C2") (pin "1") (pinfunction "1_1") (pintype "passive"))
      (node (ref "C3") (pin "1") (pinfunction "1_1") (pintype "passive"))
      (node (ref "C34") (pin "1") (pinfunction "1_1") (pintype "passive"))
      (node (ref "C37") (pin "2") (pinfunction "2_2") (pintype "passive"))
      (node (ref "C38") (pin "2") (pinfunction "2_2") (pintype "passive"))
      (node (ref "C4") (pin "1") (pinfunction "1_1") (pintype "passive"))
      (node (ref "C5") (pin "1") (pinfunction "1_1") (pintype "passive"))
      (node (ref "C53") (pin "1") (pinfunction "1_1") (pintype "passive"))
      (node (ref "C6") (pin "1") (pinfunction "1_1") (pintype "passive"))
      (node (ref "CN4") (pin "1") (pinfunction "1_1") (pintype "passive"))
      (node (ref "CN6") (pin "8") (pinfunction "8_8") (pintype "passive"))
      (node (ref "FB3") (pin "2") (pinfunction "2_2") (pintype "passive"))
      (node (ref "L1") (pin "1") (pinfunction "1_1") (pintype "passive"))
      (node (ref "R12") (pin "2") (pinfunction "2_2") (pintype "passive"))
      (node (ref "R13") (pin "2") (pinfunction "2_2") (pintype "passive"))
      (node (ref "R14") (pin "2") (pinfunction "2_2") (pintype "passive"))
      (node (ref "R15") (pin "1") (pinfunction "1_1") (pintype "passive"))
      (node (ref "R16") (pin "1") (pinfunction "1_1") (pintype "passive"))
      (node (ref "R27") (pin "1") (pinfunction "1_1") (pintype "passive"))
      (node (ref "R28") (pin "1") (pinfunction "1_1") (pintype "passive"))
      (node (ref "R6") (pin "1") (pinfunction "1_1") (pintype "passive"))
      (node (ref "U1") (pin "B1") (pinfunction "VDDIO3_B1") (pintype "passive"))
      (node (ref "U1") (pin "E3") (pinfunction "VDDIO2_E3") (pintype "passive"))
      (node (ref "U1") (pin "H11") (pinfunction "VDDIO1_H11") (pintype "passive"))
      (node (ref "U1") (pin "L9") (pinfunction "VDDIO1_L9") (pintype "passive"))
      (node (ref "U4") (pin "8") (pinfunction "VCC_8") (pintype "passive"))
      (node (ref "U5") (pin "1") (pinfunction "OUT_1") (pintype "output"))
      (node (ref "U5") (pin "18") (pinfunction "OUT_18") (pintype "output"))
      (node (ref "U5") (pin "19") (pinfunction "OUT_19") (pintype "output"))
      (node (ref "U5") (pin "20") (pinfunction "OUT_20") (pintype "output"))
    )
    (net (code "113") (name "VCC_SYS") (class "Default")
      (node (ref "C35") (pin "2") (pinfunction "2_2") (pintype "passive"))
      (node (ref "C39") (pin "1") (pinfunction "1_1") (pintype "passive"))
      (node (ref "C43") (pin "2") (pinfunction "2_2") (pintype "passive"))
      (node (ref "C47") (pin "2") (pinfunction "2_2") (pintype "passive"))
      (node (ref "C52") (pin "2") (pinfunction "2_2") (pintype "passive"))
      (node (ref "D1") (pin "2") (pinfunction "A_2") (pintype "passive"))
      (node (ref "R18") (pin "1") (pinfunction "1_1") (pintype "passive"))
      (node (ref "SW1") (pin "2") (pinfunction "2_2") (pintype "passive"))
      (node (ref "U5") (pin "10") (pinfunction "BIAS_10") (pintype "passive"))
      (node (ref "U5") (pin "11") (pinfunction "EN_11") (pintype "passive"))
      (node (ref "U5") (pin "5") (pinfunction "IN_5") (pintype "input"))
      (node (ref "U5") (pin "6") (pinfunction "IN_6") (pintype "input"))
      (node (ref "U5") (pin "7") (pinfunction "IN_7") (pintype "input"))
      (node (ref "U5") (pin "8") (pinfunction "IN_8") (pintype "input"))
      (node (ref "U6") (pin "5") (pinfunction "VIN_5") (pintype "input"))
      (node (ref "U7") (pin "10") (pinfunction "BIAS_10") (pintype "passive"))
      (node (ref "U7") (pin "11") (pinfunction "EN_11") (pintype "passive"))
      (node (ref "U7") (pin "5") (pinfunction "IN_5") (pintype "input"))
      (node (ref "U7") (pin "6") (pinfunction "IN_6") (pintype "input"))
      (node (ref "U7") (pin "7") (pinfunction "IN_7") (pintype "input"))
      (node (ref "U7") (pin "8") (pinfunction "IN_8") (pintype "input"))
      (node (ref "U8") (pin "10") (pinfunction "BIAS_10") (pintype "passive"))
      (node (ref "U8") (pin "11") (pinfunction "EN_11") (pintype "passive"))
      (node (ref "U8") (pin "5") (pinfunction "IN_5") (pintype "input"))
      (node (ref "U8") (pin "6") (pinfunction "IN_6") (pintype "input"))
      (node (ref "U8") (pin "7") (pinfunction "IN_7") (pintype "input"))
      (node (ref "U8") (pin "8") (pinfunction "IN_8") (pintype "input"))
    )
    (net (code "114") (name "VCC_USB") (class "Default")
      (node (ref "C51") (pin "2") (pinfunction "2_2") (pintype "passive"))
      (node (ref "C7") (pin "2") (pinfunction "2_2") (pintype "passive"))
      (node (ref "SW1") (pin "3") (pinfunction "3_3") (pintype "passive"))
      (node (ref "U1") (pin "E10") (pinfunction "VUSB_E10") (pintype "passive"))
      (node (ref "U2") (pin "5") (pinfunction "OUT_5") (pintype "passive"))
    )
    (net (code "115") (name "VCC_USB_RAW") (class "Default")
      (node (ref "C32") (pin "2") (pinfunction "2_2") (pintype "passive"))
      (node (ref "C33") (pin "2") (pinfunction "2_2") (pintype "passive"))
      (node (ref "FB1") (pin "2") (pinfunction "2_2") (pintype "passive"))
      (node (ref "R8") (pin "2") (pinfunction "2_2") (pintype "passive"))
      (node (ref "U2") (pin "1") (pinfunction "IN_1") (pintype "passive"))
    )
    (net (code "116") (name "unconnected-(CN1-ID-Pad4)") (class "Default")
      (node (ref "CN1") (pin "4") (pinfunction "ID_4") (pintype "passive"))
    )
    (net (code "117") (name "unconnected-(CN3-Pad7)") (class "Default")
      (node (ref "CN3") (pin "7") (pinfunction "7_7") (pintype "passive"))
    )
    (net (code "118") (name "unconnected-(U1A-HSYNC_test-PadG6)") (class "Default")
      (node (ref "U1") (pin "G6") (pinfunction "HSYNC_test_G6") (pintype "passive"))
    )
    (net (code "119") (name "unconnected-(U1A-I2S_CLK-PadD1)") (class "Default")
      (node (ref "U1") (pin "D1") (pinfunction "I2S_CLK_D1") (pintype "passive"))
    )
    (net (code "120") (name "unconnected-(U1A-I2S_MCLK-PadC11)") (class "Default")
      (node (ref "U1") (pin "C11") (pinfunction "I2S_MCLK_C11") (pintype "passive"))
    )
    (net (code "121") (name "unconnected-(U1A-I2S_SD-PadD2)") (class "Default")
      (node (ref "U1") (pin "D2") (pinfunction "I2S_SD_D2") (pintype "passive"))
    )
    (net (code "122") (name "unconnected-(U1A-I2S_WS-PadD3)") (class "Default")
      (node (ref "U1") (pin "D3") (pinfunction "I2S_WS_D3") (pintype "passive"))
    )
    (net (code "123") (name "unconnected-(U1A-PCLK_test-PadH8)") (class "Default")
      (node (ref "U1") (pin "H8") (pinfunction "PCLK_test_H8") (pintype "passive"))
    )
    (net (code "124") (name "unconnected-(U1A-UART_CTS-PadE1)") (class "Default")
      (node (ref "U1") (pin "E1") (pinfunction "UART_CTS_E1") (pintype "passive"))
    )
    (net (code "125") (name "unconnected-(U1A-UART_RTS-PadF5)") (class "Default")
      (node (ref "U1") (pin "F5") (pinfunction "UART_RTS_F5") (pintype "passive"))
    )
    (net (code "126") (name "unconnected-(U1A-UART_RX-PadE4)") (class "Default")
      (node (ref "U1") (pin "E4") (pinfunction "UART_RX_E4") (pintype "passive"))
    )
    (net (code "127") (name "unconnected-(U1A-UART_TX-PadE5)") (class "Default")
      (node (ref "U1") (pin "E5") (pinfunction "UART_TX_E5") (pintype "passive"))
    )
    (net (code "128") (name "unconnected-(U1A-VSYNC_test-PadH5)") (class "Default")
      (node (ref "U1") (pin "H5") (pinfunction "VSYNC_test_H5") (pintype "passive"))
    )
    (net (code "129") (name "unconnected-(U5-NC-Pad2)") (class "Default")
      (node (ref "U5") (pin "2") (pinfunction "NC_2") (pintype "passive"))
    )
    (net (code "130") (name "unconnected-(U5-NC-Pad3)") (class "Default")
      (node (ref "U5") (pin "3") (pinfunction "NC_3") (pintype "passive"))
    )
    (net (code "131") (name "unconnected-(U5-NC-Pad4)") (class "Default")
      (node (ref "U5") (pin "4") (pinfunction "NC_4") (pintype "passive"))
    )
    (net (code "132") (name "unconnected-(U5-NC-Pad13)") (class "Default")
      (node (ref "U5") (pin "13") (pinfunction "NC_13") (pintype "passive"))
    )
    (net (code "133") (name "unconnected-(U5-NC-Pad14)") (class "Default")
      (node (ref "U5") (pin "14") (pinfunction "NC_14") (pintype "passive"))
    )
    (net (code "134") (name "unconnected-(U5-NC-Pad17)") (class "Default")
      (node (ref "U5") (pin "17") (pinfunction "NC_17") (pintype "passive"))
    )
    (net (code "135") (name "unconnected-(U7-NC-Pad2)") (class "Default")
      (node (ref "U7") (pin "2") (pinfunction "NC_2") (pintype "passive"))
    )
    (net (code "136") (name "unconnected-(U7-NC-Pad3)") (class "Default")
      (node (ref "U7") (pin "3") (pinfunction "NC_3") (pintype "passive"))
    )
    (net (code "137") (name "unconnected-(U7-NC-Pad4)") (class "Default")
      (node (ref "U7") (pin "4") (pinfunction "NC_4") (pintype "passive"))
    )
    (net (code "138") (name "unconnected-(U7-NC-Pad13)") (class "Default")
      (node (ref "U7") (pin "13") (pinfunction "NC_13") (pintype "passive"))
    )
    (net (code "139") (name "unconnected-(U7-NC-Pad14)") (class "Default")
      (node (ref "U7") (pin "14") (pinfunction "NC_14") (pintype "passive"))
    )
    (net (code "140") (name "unconnected-(U7-NC-Pad17)") (class "Default")
      (node (ref "U7") (pin "17") (pinfunction "NC_17") (pintype "passive"))
    )
    (net (code "141") (name "unconnected-(U8-NC-Pad2)") (class "Default")
      (node (ref "U8") (pin "2") (pinfunction "NC_2") (pintype "passive"))
    )
    (net (code "142") (name "unconnected-(U8-NC-Pad3)") (class "Default")
      (node (ref "U8") (pin "3") (pinfunction "NC_3") (pintype "passive"))
    )
    (net (code "143") (name "unconnected-(U8-NC-Pad4)") (class "Default")
      (node (ref "U8") (pin "4") (pinfunction "NC_4") (pintype "passive"))
    )
    (net (code "144") (name "unconnected-(U8-NC-Pad13)") (class "Default")
      (node (ref "U8") (pin "13") (pinfunction "NC_13") (pintype "passive"))
    )
    (net (code "145") (name "unconnected-(U8-NC-Pad14)") (class "Default")
      (node (ref "U8") (pin "14") (pinfunction "NC_14") (pintype "passive"))
    )
    (net (code "146") (name "unconnected-(U8-NC-Pad17)") (class "Default")
      (node (ref "U8") (pin "17") (pinfunction "NC_17") (pintype "passive"))
    )
    (net (code "147") (name "unconnected-(U8-SS-Pad15)") (class "Default")
      (node (ref "U8") (pin "15") (pinfunction "SS_15") (pintype "passive"))
    )
    (net (code "148") (name "unconnected-(Y1-NC-Pad1)") (class "Default")
      (node (ref "Y1") (pin "1") (pinfunction "NC_1") (pintype "passive"))
    )
  )
)
